# main_board_v1_2.net
KiCad netlist of a schematic drawn in EAGLE
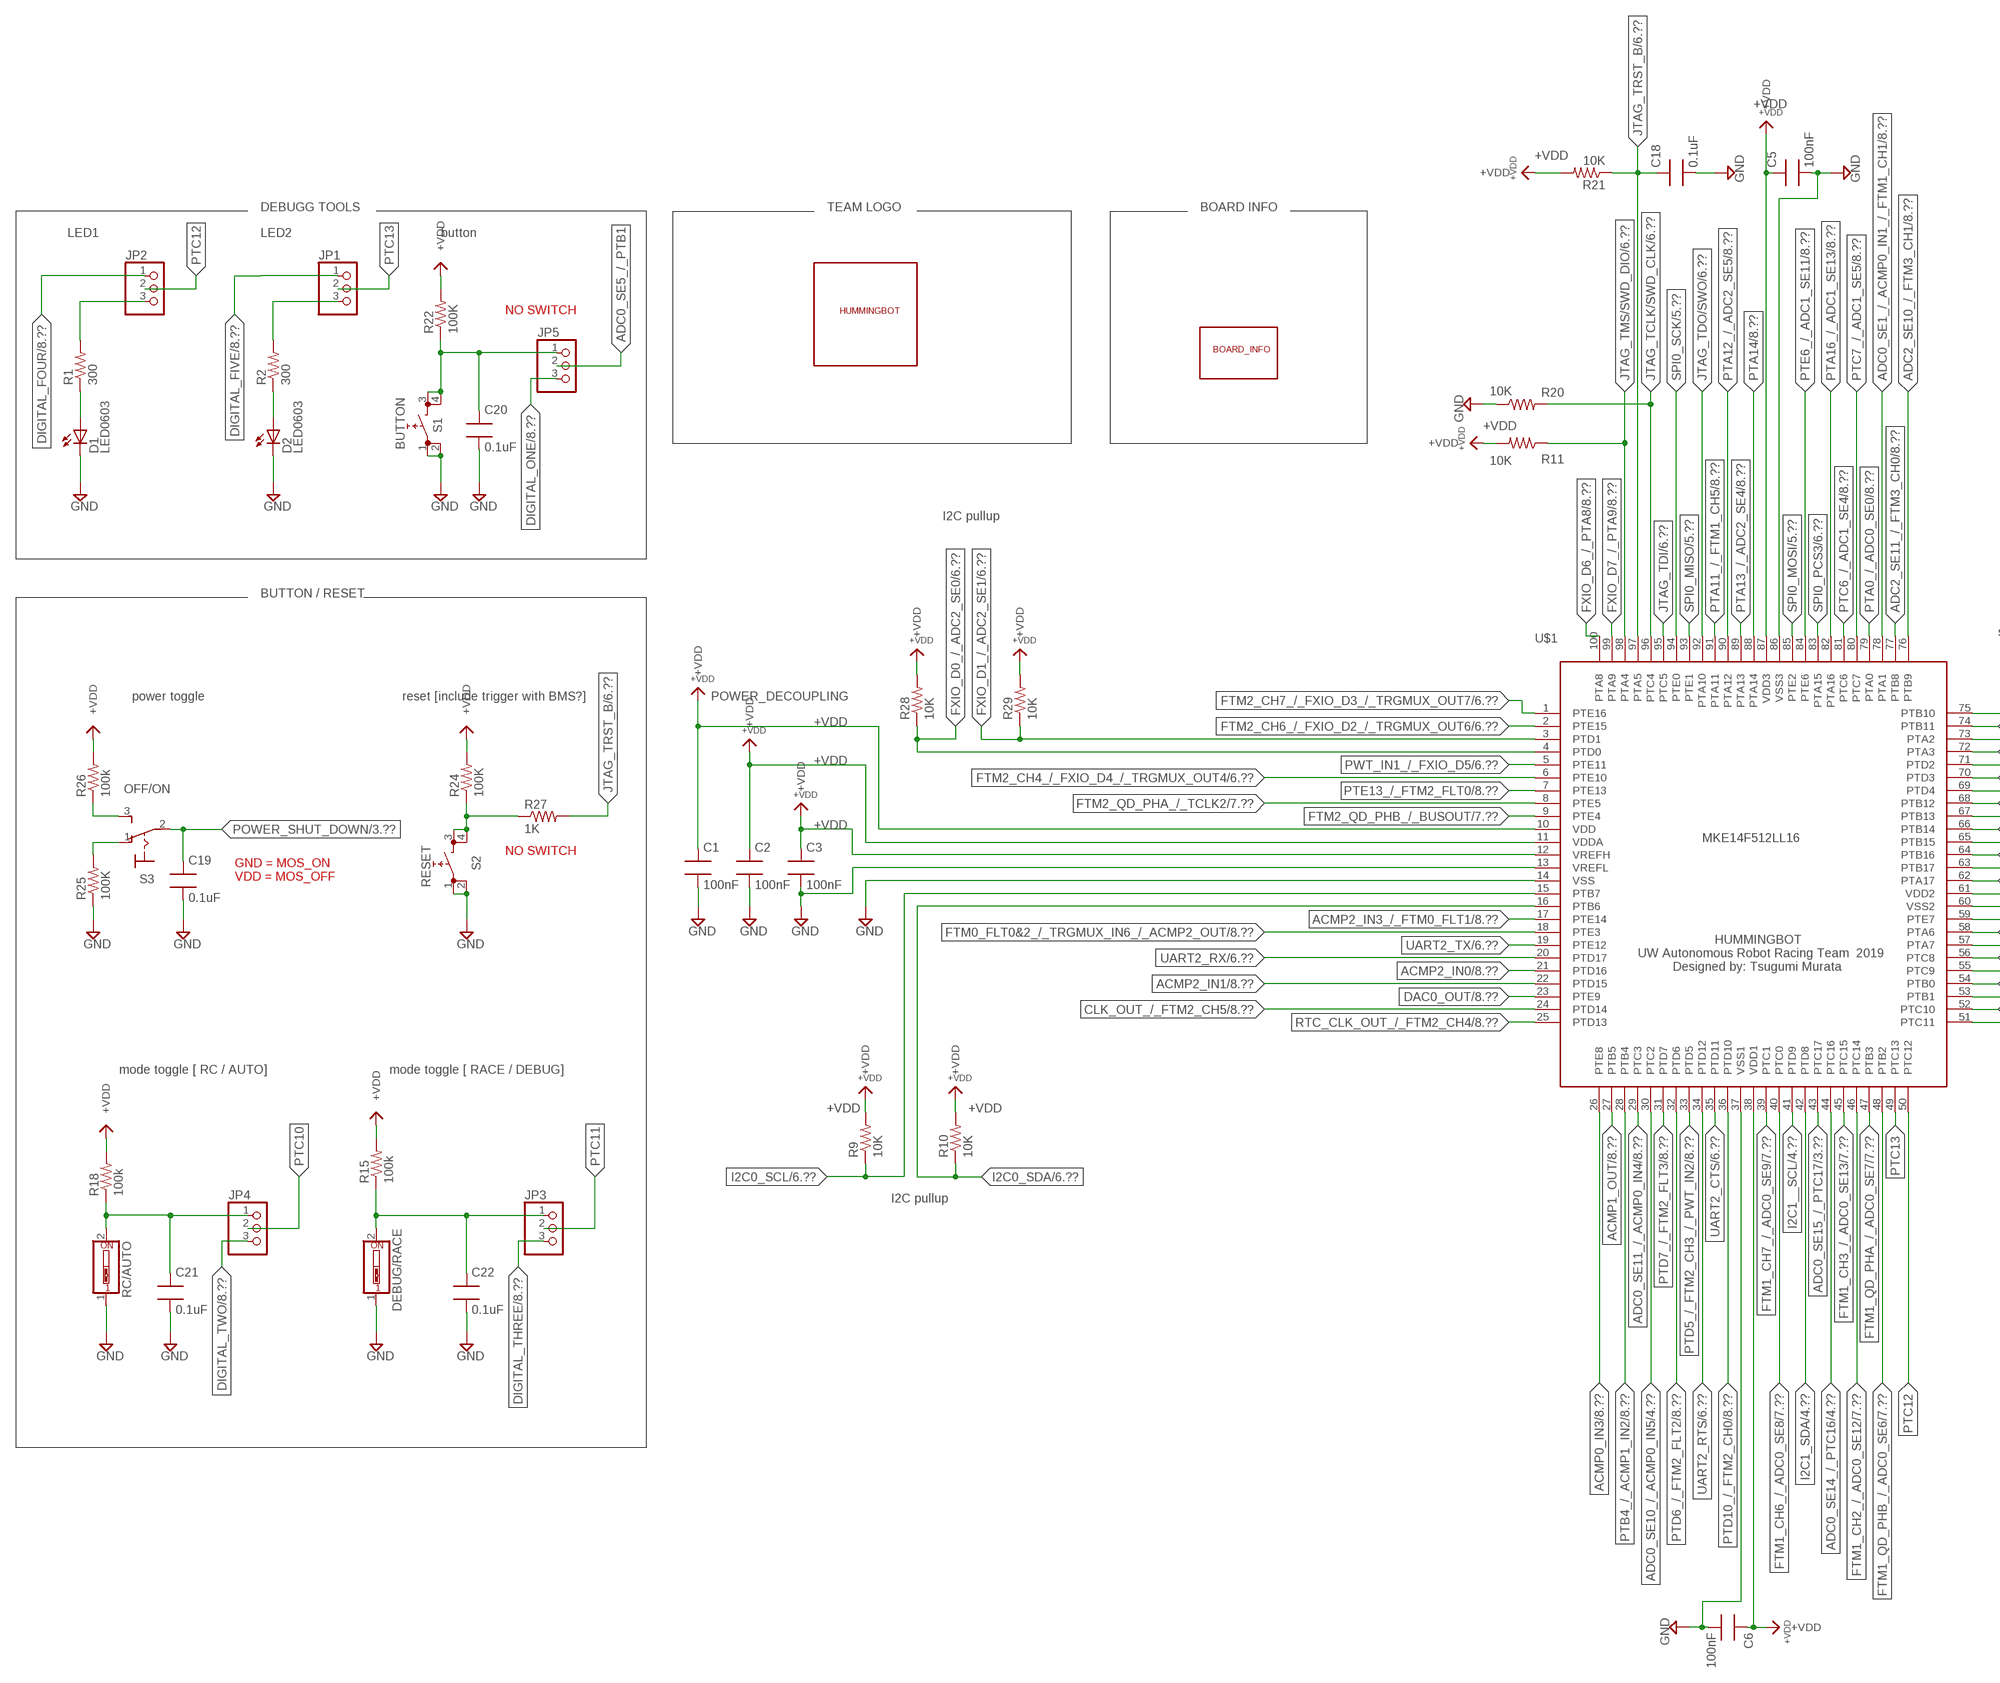
[diagram p0: schematic, sheet 1, part 1 of 2]
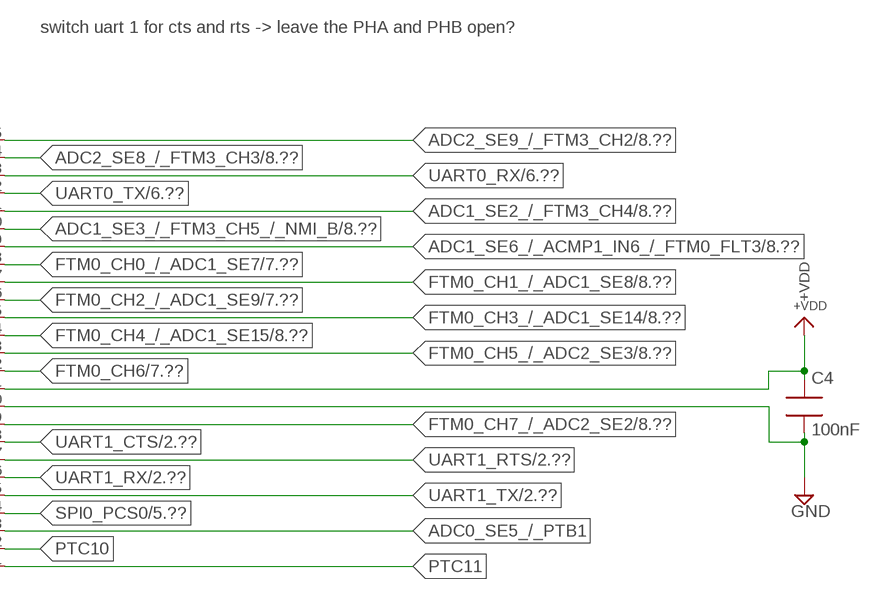
[diagram p1: schematic, sheet 1, part 2 of 2]
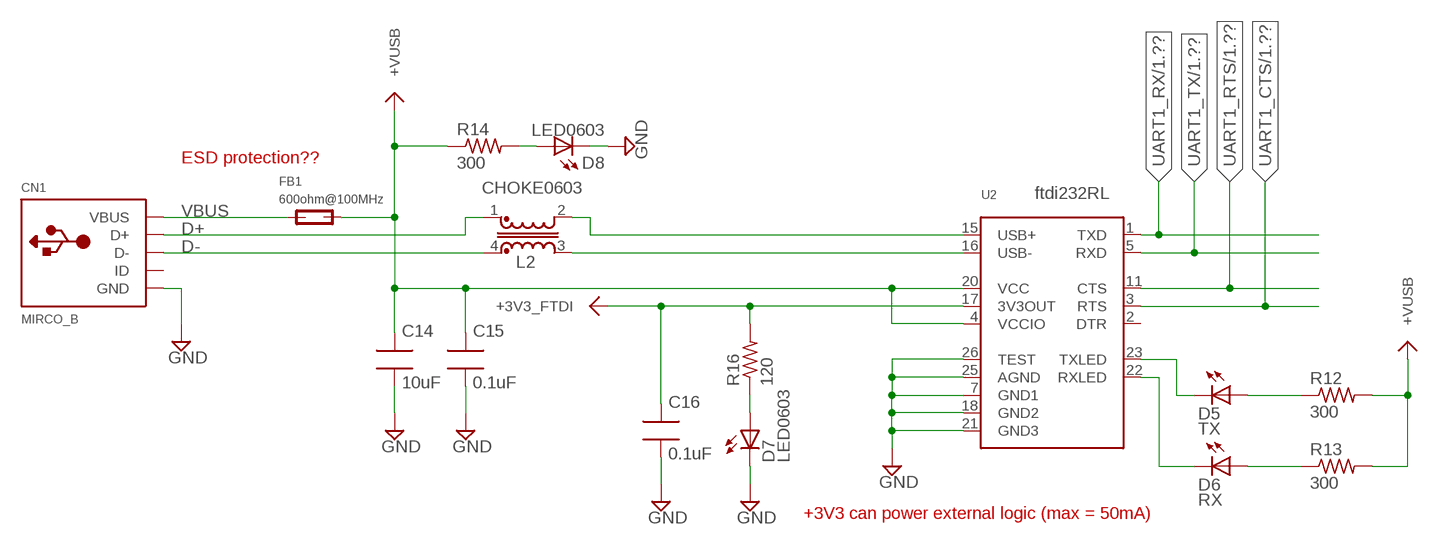
[diagram p2: schematic, sheet 2]
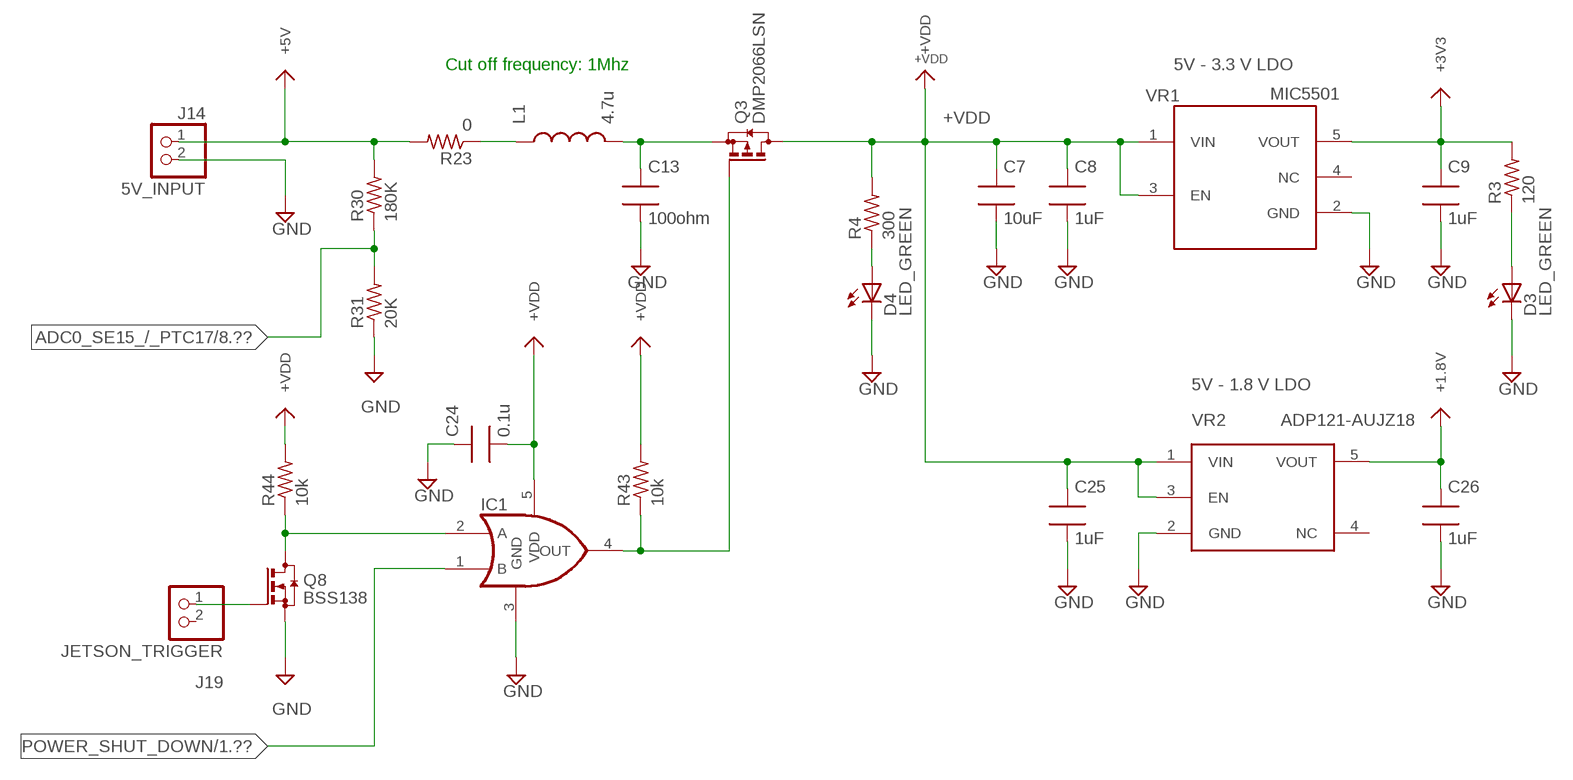
[diagram p3: schematic, sheet 3]
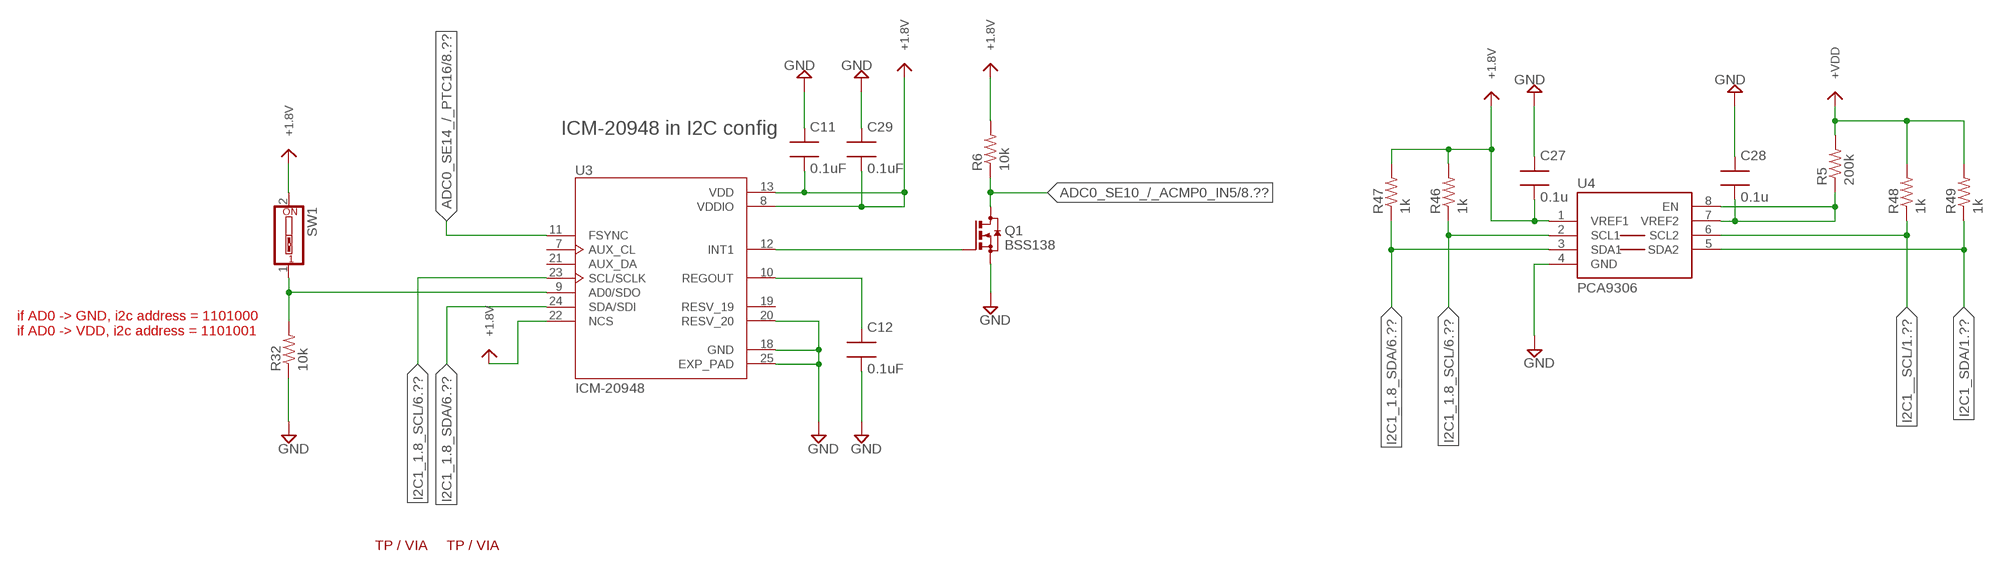
[diagram p4: schematic, sheet 4]
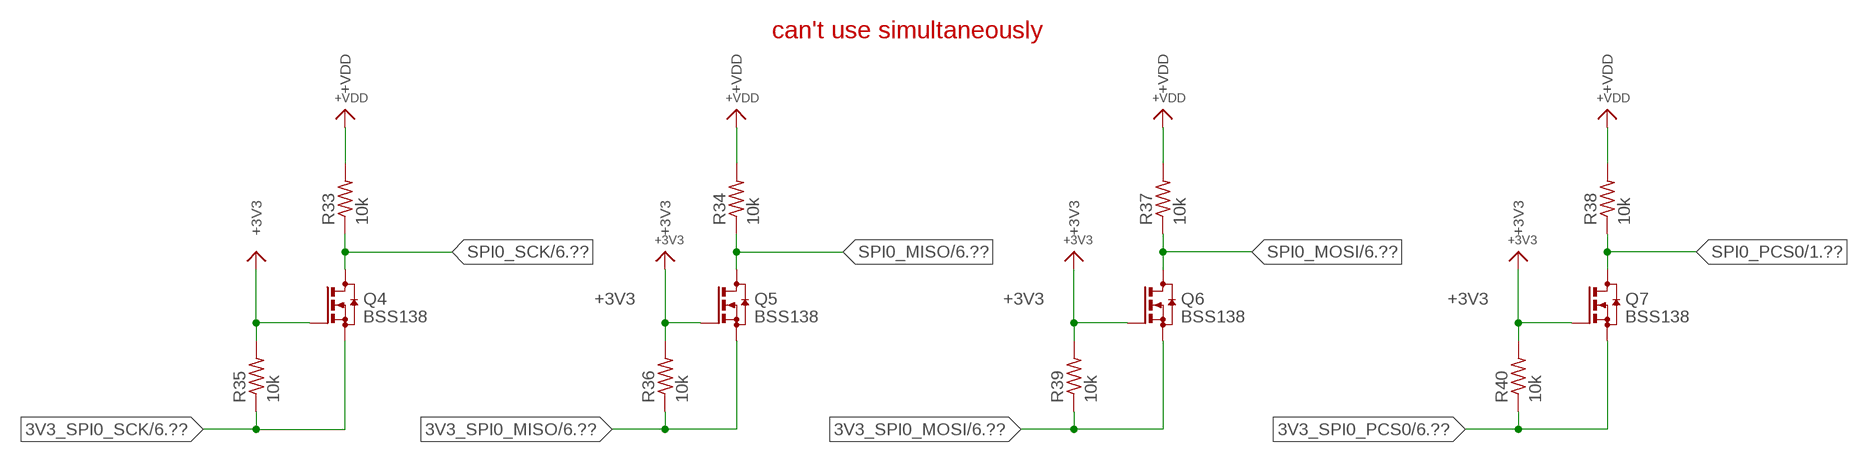
[diagram p5: schematic, sheet 5]
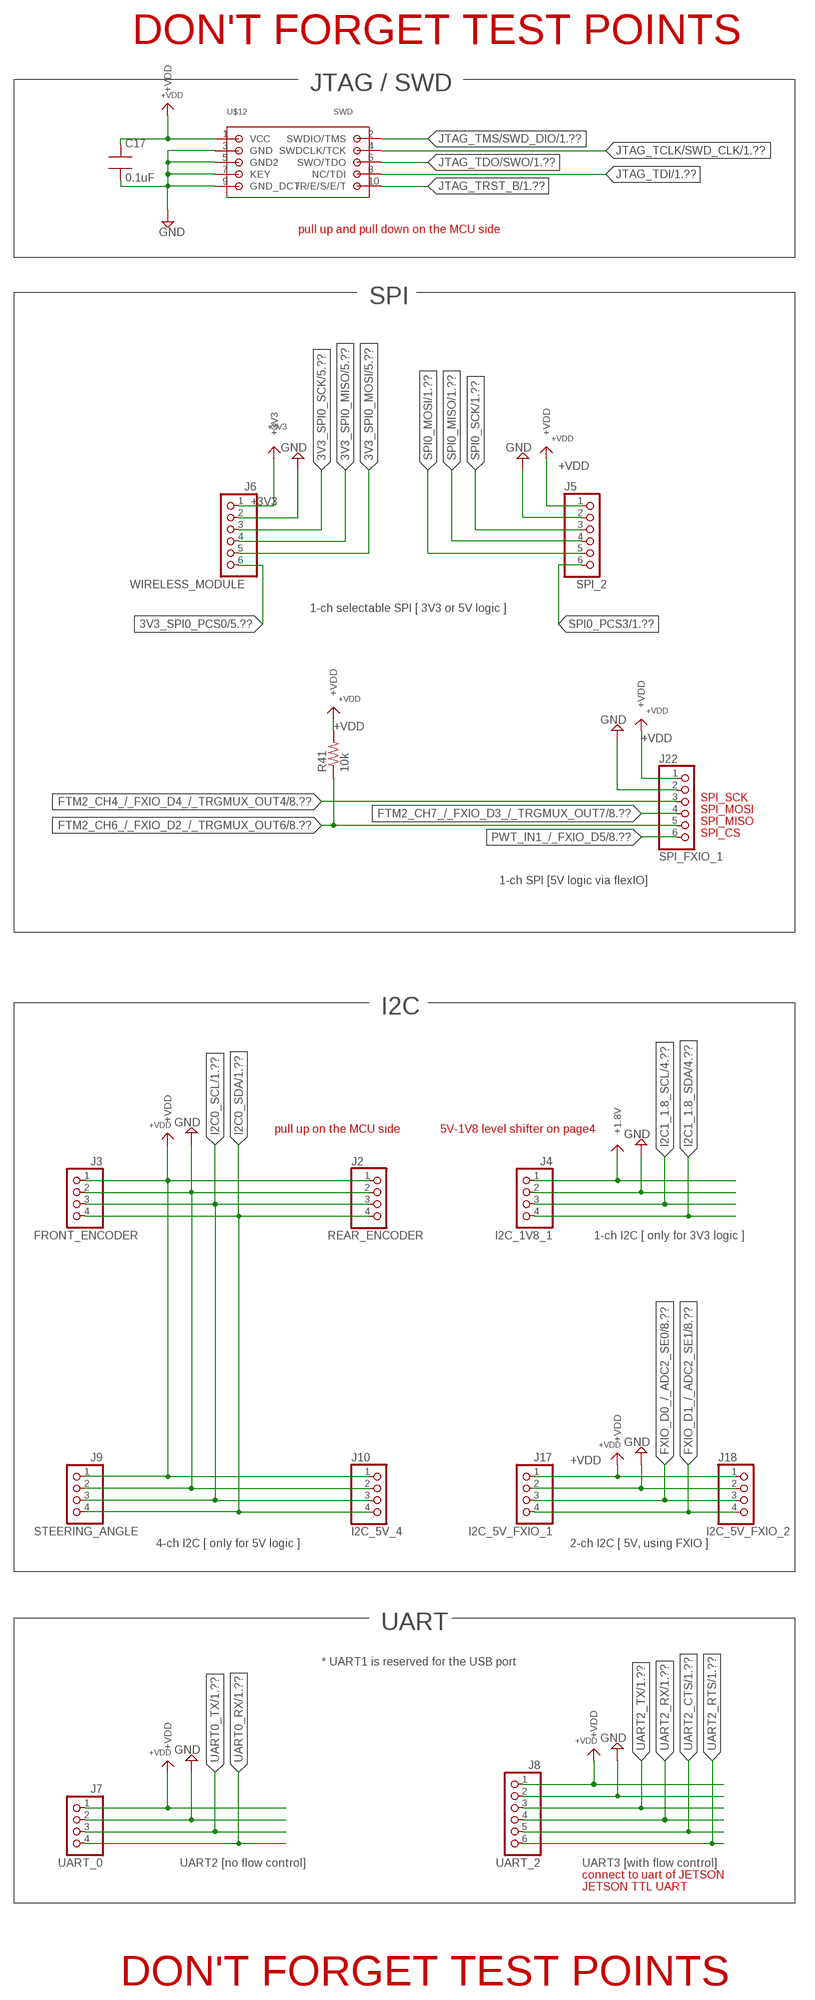
[diagram p6: schematic, sheet 6]
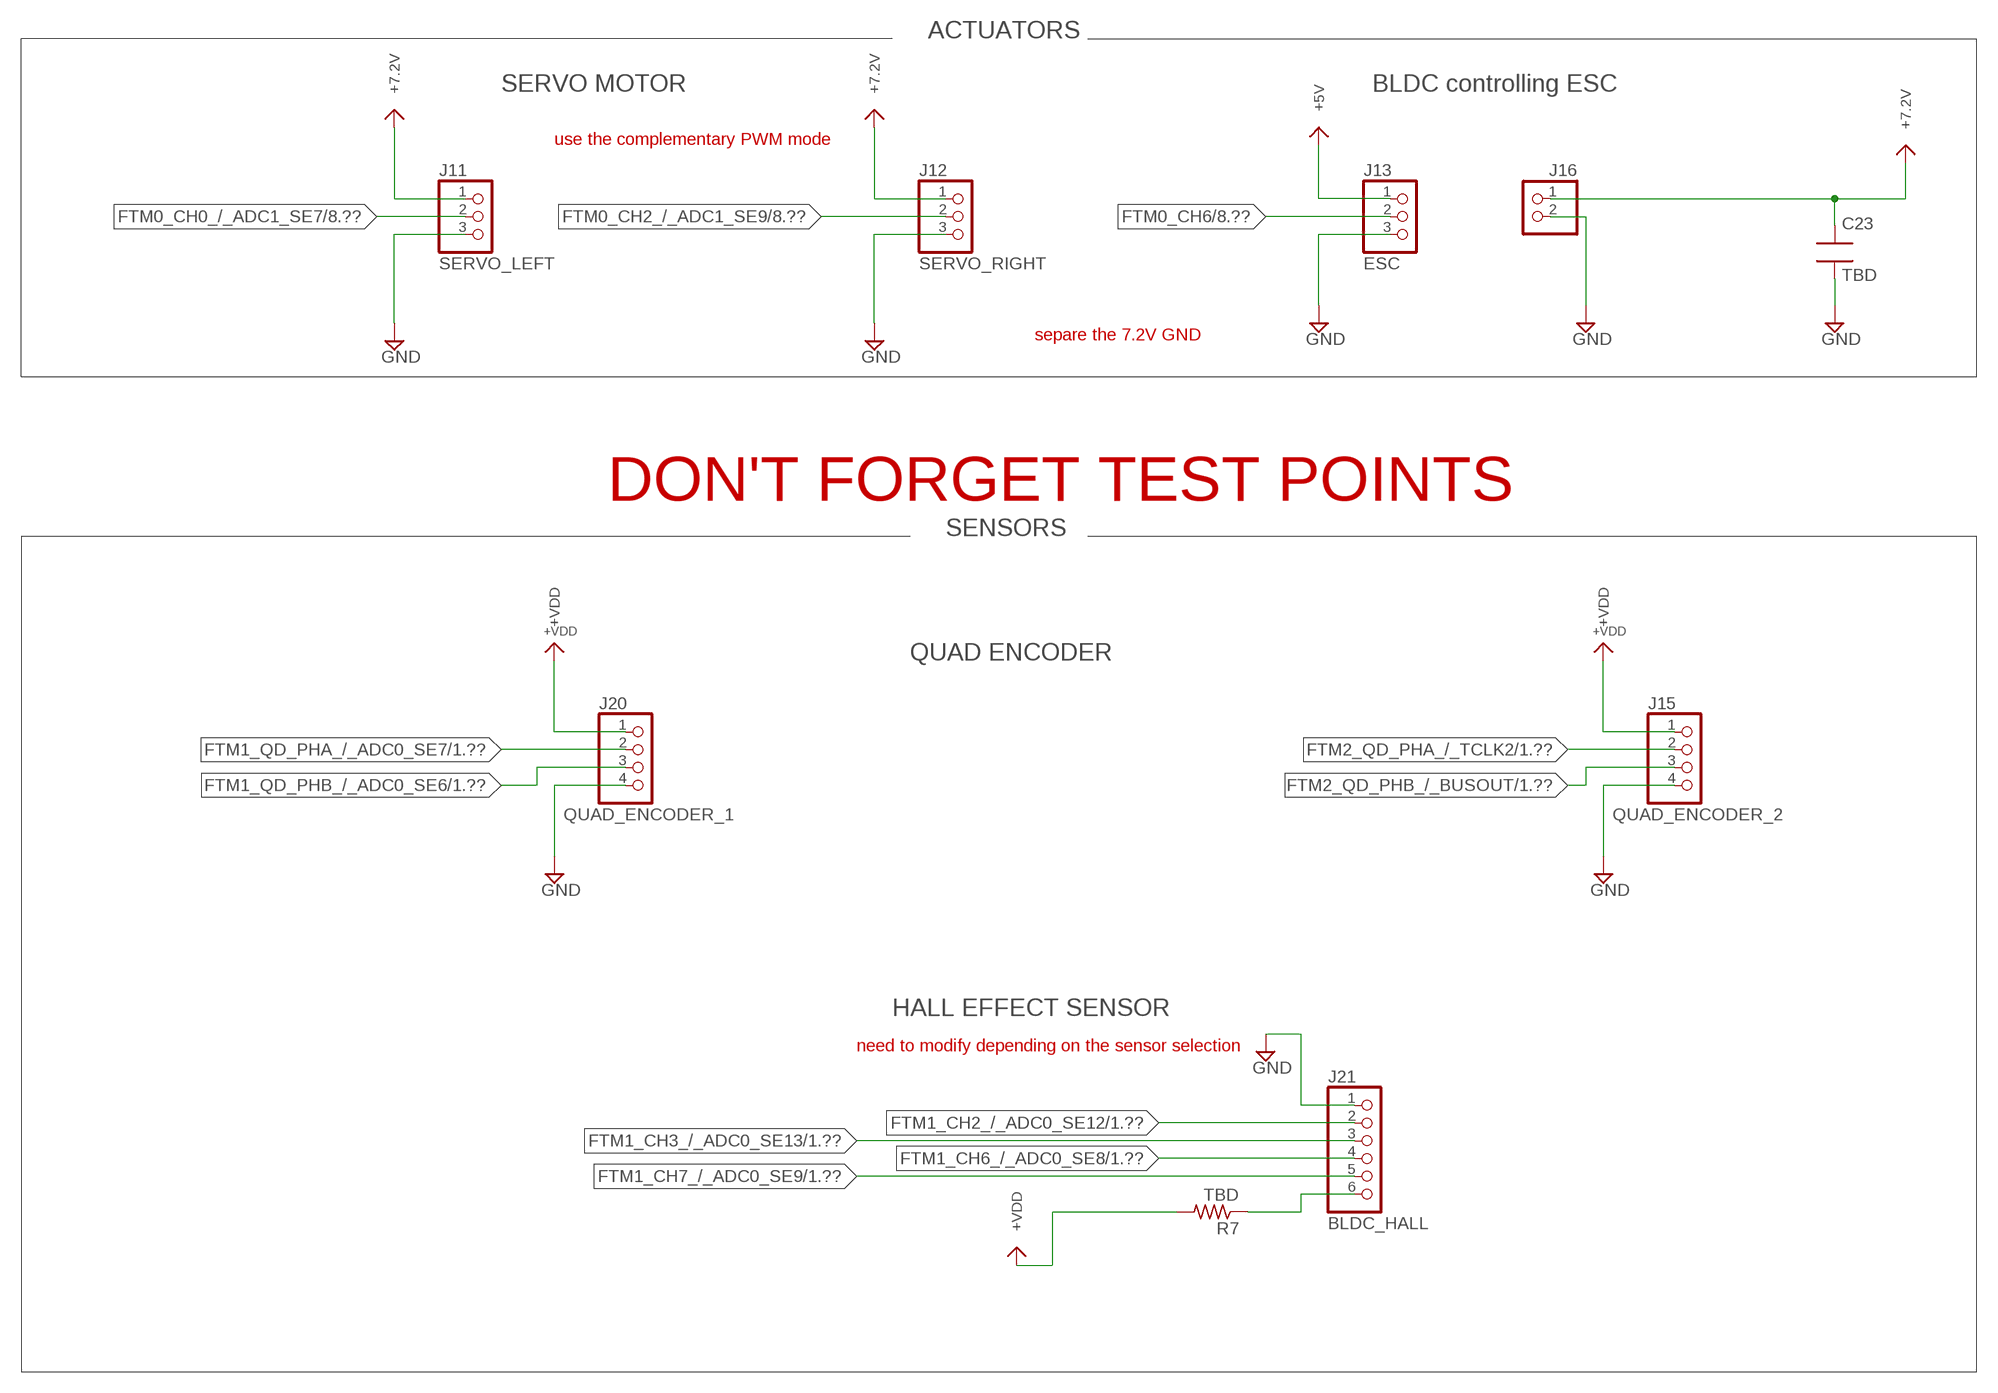
[diagram p7: schematic, sheet 7]
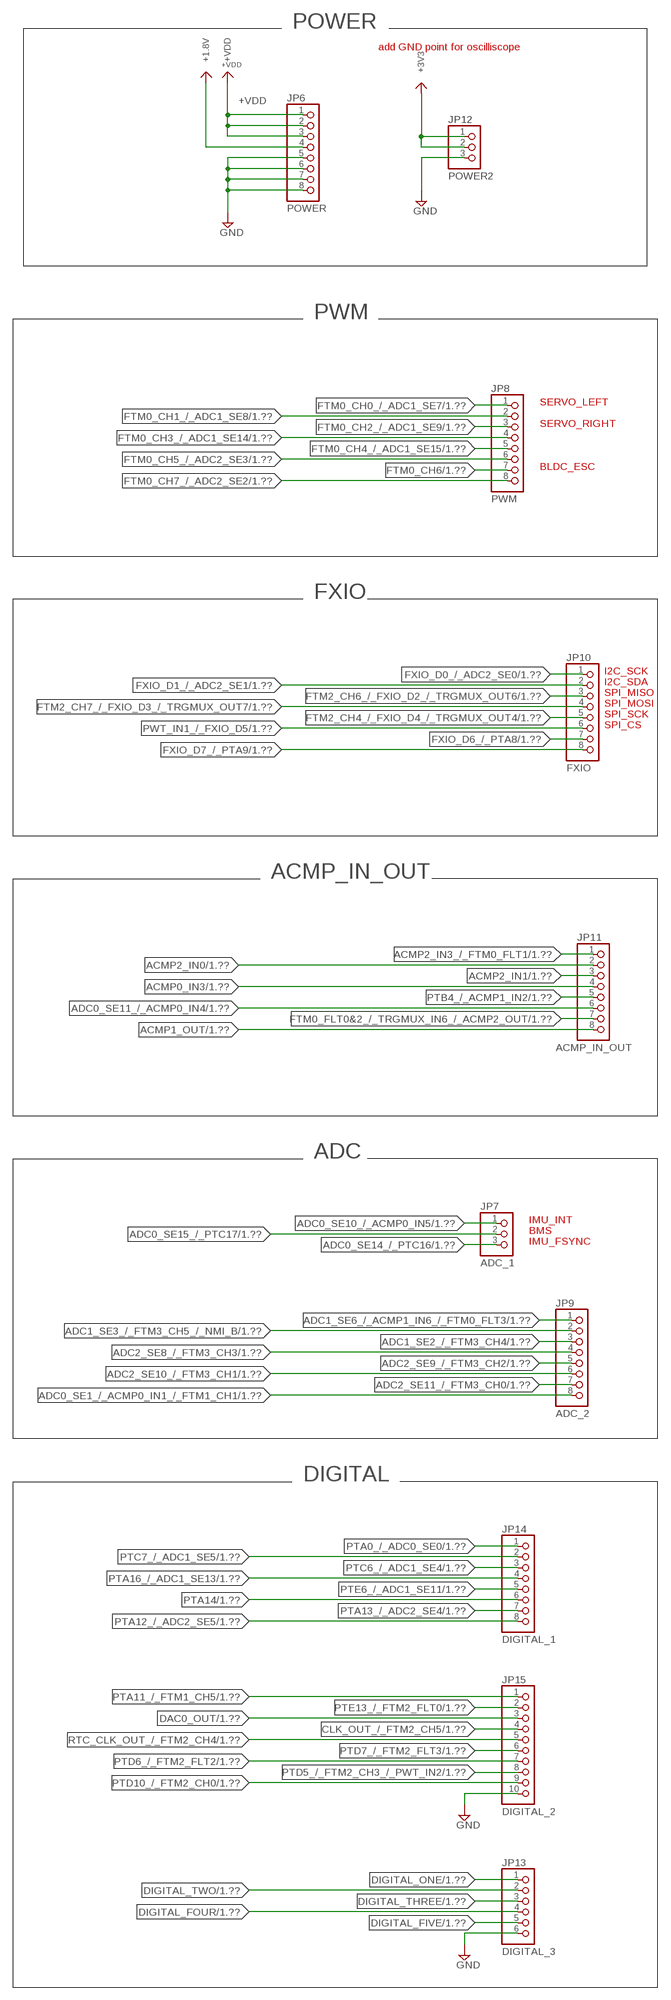
[diagram p8: schematic, sheet 8]

(export (version "E")
  (design (tool "Eeschema 10.0.6"))
  (components
    (comp (ref "C7")
      (value "10uF")
      (footprint "eagle-import:0603SMT")
      (libsource (lib "eagle-import") (part "CAP0603"))
    )
    (comp (ref "C8")
      (value "1uF")
      (footprint "eagle-import:0603SMT")
      (libsource (lib "eagle-import") (part "CAP0603"))
    )
    (comp (ref "C9")
      (value "1uF")
      (footprint "eagle-import:0603SMT")
      (libsource (lib "eagle-import") (part "CAP0603"))
    )
    (comp (ref "C13")
      (value "100ohm")
      (footprint "eagle-import:0603SMT")
      (libsource (lib "eagle-import") (part "CAP0603"))
    )
    (comp (ref "C24")
      (value "0.1u")
      (footprint "eagle-import:0603SMT")
      (libsource (lib "eagle-import") (part "CAP0603"))
    )
    (comp (ref "C25")
      (value "1uF")
      (footprint "eagle-import:0603SMT")
      (libsource (lib "eagle-import") (part "CAP0603"))
    )
    (comp (ref "C26")
      (value "1uF")
      (footprint "eagle-import:0603SMT")
      (libsource (lib "eagle-import") (part "CAP0603"))
    )
    (comp (ref "D3")
      (value "LED_GREEN")
      (footprint "eagle-import:0603SMT")
      (libsource (lib "eagle-import") (part "LED0603"))
    )
    (comp (ref "D4")
      (value "LED_GREEN")
      (footprint "eagle-import:0603SMT")
      (libsource (lib "eagle-import") (part "LED0603"))
    )
    (comp (ref "IC1")
      (value "OR_SC70-5")
      (footprint "eagle-import:SC70-5")
      (libsource (lib "eagle-import") (part "OR_SC70-5"))
    )
    (comp (ref "J14")
      (value "5V_INPUT")
      (footprint "eagle-import:JST_B2B-PH-K-S(LF)(SN)")
      (libsource (lib "eagle-import") (part "PINHEAD-2-VERTICAL"))
    )
    (comp (ref "J19")
      (value "JETSON_TRIGGER")
      (footprint "eagle-import:JST_B2B-PH-K-S(LF)(SN)")
      (libsource (lib "eagle-import") (part "PINHEAD-2-VERTICAL"))
    )
    (comp (ref "L1")
      (value "4.7u")
      (footprint "eagle-import:0603SMT")
      (libsource (lib "eagle-import") (part "IND0603"))
    )
    (comp (ref "Q3")
      (value "DMP2066LSN")
      (footprint "eagle-import:SOT23")
      (libsource (lib "eagle-import") (part "PMOS_SOT23"))
    )
    (comp (ref "Q8")
      (value "BSS138")
      (footprint "eagle-import:SOT23")
      (libsource (lib "eagle-import") (part "NMOS_SOT23"))
    )
    (comp (ref "R3")
      (value "120")
      (footprint "eagle-import:0603SMT")
      (libsource (lib "eagle-import") (part "RES0603"))
    )
    (comp (ref "R4")
      (value "300")
      (footprint "eagle-import:0603SMT")
      (libsource (lib "eagle-import") (part "RES0603"))
    )
    (comp (ref "R23")
      (value "0")
      (footprint "eagle-import:0603SMT")
      (libsource (lib "eagle-import") (part "RES0603"))
    )
    (comp (ref "R30")
      (value "180K")
      (footprint "eagle-import:0603SMT")
      (libsource (lib "eagle-import") (part "RES0603"))
    )
    (comp (ref "R31")
      (value "20K")
      (footprint "eagle-import:0603SMT")
      (libsource (lib "eagle-import") (part "RES0603"))
    )
    (comp (ref "R43")
      (value "10k")
      (footprint "eagle-import:0603SMT")
      (libsource (lib "eagle-import") (part "RES0603"))
    )
    (comp (ref "R44")
      (value "10k")
      (footprint "eagle-import:0603SMT")
      (libsource (lib "eagle-import") (part "RES0603"))
    )
    (comp (ref "VR1")
      (value "MIC5501")
      (footprint "eagle-import:SOT23-5")
      (libsource (lib "eagle-import") (part "MIC5501"))
    )
    (comp (ref "VR2")
      (value "ADP121-AUJZ18")
      (footprint "eagle-import:TSOT23-5")
      (libsource (lib "eagle-import") (part "ADP121"))
    )
    (comp (ref "C14")
      (value "10uF")
      (footprint "eagle-import:0603SMT")
      (libsource (lib "eagle-import") (part "CAP0603"))
    )
    (comp (ref "C15")
      (value "0.1uF")
      (footprint "eagle-import:0603SMT")
      (libsource (lib "eagle-import") (part "CAP0603"))
    )
    (comp (ref "C16")
      (value "0.1uF")
      (footprint "eagle-import:0603SMT")
      (libsource (lib "eagle-import") (part "CAP0603"))
    )
    (comp (ref "CN1")
      (value "MIRCO_B")
      (footprint "eagle-import:MICRO-USB")
      (libsource (lib "eagle-import") (part "MIRCO_B"))
    )
    (comp (ref "D5")
      (value "TX")
      (footprint "eagle-import:0603SMT")
      (libsource (lib "eagle-import") (part "LED0603"))
    )
    (comp (ref "D6")
      (value "RX")
      (footprint "eagle-import:0603SMT")
      (libsource (lib "eagle-import") (part "LED0603"))
    )
    (comp (ref "D7")
      (value "LED0603")
      (footprint "eagle-import:0603SMT")
      (libsource (lib "eagle-import") (part "LED0603"))
    )
    (comp (ref "D8")
      (value "LED0603")
      (footprint "eagle-import:0603SMT")
      (libsource (lib "eagle-import") (part "LED0603"))
    )
    (comp (ref "FB1")
      (value "600ohm@100MHz")
      (footprint "eagle-import:0603SMT")
      (libsource (lib "eagle-import") (part "FERRITE_BEAD"))
    )
    (comp (ref "L2")
      (value "CHOKE0603")
      (footprint "eagle-import:CHOKE0603")
      (libsource (lib "eagle-import") (part "CHOKE0603"))
    )
    (comp (ref "R12")
      (value "300")
      (footprint "eagle-import:0603SMT")
      (libsource (lib "eagle-import") (part "RES0603"))
    )
    (comp (ref "R13")
      (value "300")
      (footprint "eagle-import:0603SMT")
      (libsource (lib "eagle-import") (part "RES0603"))
    )
    (comp (ref "R14")
      (value "300")
      (footprint "eagle-import:0603SMT")
      (libsource (lib "eagle-import") (part "RES0603"))
    )
    (comp (ref "R16")
      (value "120")
      (footprint "eagle-import:0603SMT")
      (libsource (lib "eagle-import") (part "RES0603"))
    )
    (comp (ref "U2")
      (value "FT232RLSSOP28")
      (footprint "eagle-import:SSOP28DB")
      (libsource (lib "eagle-import") (part "FT232RLSSOP28"))
    )
    (comp (ref "C23")
      (value "TBD")
      (footprint "eagle-import:0603SMT")
      (libsource (lib "eagle-import") (part "CAP0603"))
    )
    (comp (ref "J11")
      (value "SERVO_LEFT")
      (footprint "eagle-import:JST_B3B-PH-K-S(LF)(SN)")
      (libsource (lib "eagle-import") (part "PINHEAD-3-VERTICAL"))
    )
    (comp (ref "J12")
      (value "SERVO_RIGHT")
      (footprint "eagle-import:JST_B3B-PH-K-S(LF)(SN)")
      (libsource (lib "eagle-import") (part "PINHEAD-3-VERTICAL"))
    )
    (comp (ref "J13")
      (value "ESC")
      (footprint "eagle-import:JST_B3B-PH-K-S(LF)(SN)")
      (libsource (lib "eagle-import") (part "PINHEAD-3-VERTICAL"))
    )
    (comp (ref "J15")
      (value "QUAD_ENCODER_2")
      (footprint "eagle-import:JST_B4B-PH-K-S(LF)(SN)")
      (libsource (lib "eagle-import") (part "PINHEAD-4-VERTICAL"))
    )
    (comp (ref "J16")
      (value "7.2V_INPUT")
      (footprint "eagle-import:JST_B2B-PH-K-S(LF)(SN)")
      (libsource (lib "eagle-import") (part "PINHEAD-2-VERTICAL"))
    )
    (comp (ref "J20")
      (value "QUAD_ENCODER_1")
      (footprint "eagle-import:JST_B4B-PH-K-S(LF)(SN)")
      (libsource (lib "eagle-import") (part "PINHEAD-4-VERTICAL"))
    )
    (comp (ref "J21")
      (value "BLDC_HALL")
      (footprint "eagle-import:JST_B6B-PH-K-S(LF)(SN)")
      (libsource (lib "eagle-import") (part "PINHEAD-6-VERTICAL"))
    )
    (comp (ref "R7")
      (value "TBD")
      (footprint "eagle-import:0603SMT")
      (libsource (lib "eagle-import") (part "RES0603"))
    )
    (comp (ref "C17")
      (value "0.1uF")
      (footprint "eagle-import:0603SMT")
      (fields (field (name "SPICEPREFIX") "C"))
      (libsource (lib "eagle-import") (part "CAP0603"))
    )
    (comp (ref "J2")
      (value "REAR_ENCODER")
      (footprint "eagle-import:JST_B4B-PH-K-S(LF)(SN)")
      (libsource (lib "eagle-import") (part "PINHEAD-4-VERTICAL"))
    )
    (comp (ref "J3")
      (value "FRONT_ENCODER")
      (footprint "eagle-import:JST_B4B-PH-K-S(LF)(SN)")
      (libsource (lib "eagle-import") (part "PINHEAD-4-VERTICAL"))
    )
    (comp (ref "J4")
      (value "I2C_1V8_1")
      (footprint "eagle-import:JST_B4B-PH-K-S(LF)(SN)")
      (libsource (lib "eagle-import") (part "PINHEAD-4-VERTICAL"))
    )
    (comp (ref "J5")
      (value "SPI_2")
      (footprint "eagle-import:JST_B6B-PH-K-S(LF)(SN)")
      (libsource (lib "eagle-import") (part "PINHEAD-6-VERTICAL"))
    )
    (comp (ref "J6")
      (value "WIRELESS_MODULE")
      (footprint "eagle-import:JST_B6B-PH-K-S(LF)(SN)")
      (libsource (lib "eagle-import") (part "PINHEAD-6-VERTICAL"))
    )
    (comp (ref "J7")
      (value "UART_0")
      (footprint "eagle-import:JST_B4B-PH-K-S(LF)(SN)")
      (libsource (lib "eagle-import") (part "PINHEAD-4-VERTICAL"))
    )
    (comp (ref "J8")
      (value "UART_2")
      (footprint "eagle-import:JST_B6B-PH-K-S(LF)(SN)")
      (libsource (lib "eagle-import") (part "PINHEAD-6-VERTICAL"))
    )
    (comp (ref "J9")
      (value "STEERING_ANGLE")
      (footprint "eagle-import:JST_B4B-PH-K-S(LF)(SN)")
      (libsource (lib "eagle-import") (part "PINHEAD-4-VERTICAL"))
    )
    (comp (ref "J10")
      (value "I2C_5V_4")
      (footprint "eagle-import:JST_B4B-PH-K-S(LF)(SN)")
      (libsource (lib "eagle-import") (part "PINHEAD-4-VERTICAL"))
    )
    (comp (ref "J17")
      (value "I2C_5V_FXIO_1")
      (footprint "eagle-import:JST_B4B-PH-K-S(LF)(SN)")
      (libsource (lib "eagle-import") (part "PINHEAD-4-VERTICAL"))
    )
    (comp (ref "J18")
      (value "I2C_5V_FXIO_2")
      (footprint "eagle-import:JST_B4B-PH-K-S(LF)(SN)")
      (libsource (lib "eagle-import") (part "PINHEAD-4-VERTICAL"))
    )
    (comp (ref "J22")
      (value "SPI_FXIO_1")
      (footprint "eagle-import:JST_B6B-PH-K-S(LF)(SN)")
      (libsource (lib "eagle-import") (part "PINHEAD-6-VERTICAL"))
    )
    (comp (ref "R41")
      (value "10k")
      (footprint "eagle-import:0603SMT")
      (libsource (lib "eagle-import") (part "RES0603"))
    )
    (comp (ref "U$12")
      (value "SWD")
      (footprint "eagle-import:SWD_1.27MM")
      (libsource (lib "eagle-import") (part "SWD_1.27MM"))
    )
    (comp (ref "Q4")
      (value "BSS138")
      (footprint "eagle-import:SOT23")
      (libsource (lib "eagle-import") (part "NMOS_SOT23"))
    )
    (comp (ref "Q5")
      (value "BSS138")
      (footprint "eagle-import:SOT23")
      (libsource (lib "eagle-import") (part "NMOS_SOT23"))
    )
    (comp (ref "Q6")
      (value "BSS138")
      (footprint "eagle-import:SOT23")
      (libsource (lib "eagle-import") (part "NMOS_SOT23"))
    )
    (comp (ref "Q7")
      (value "BSS138")
      (footprint "eagle-import:SOT23")
      (libsource (lib "eagle-import") (part "NMOS_SOT23"))
    )
    (comp (ref "R33")
      (value "10k")
      (footprint "eagle-import:0603SMT")
      (libsource (lib "eagle-import") (part "RES0603"))
    )
    (comp (ref "R34")
      (value "10k")
      (footprint "eagle-import:0603SMT")
      (libsource (lib "eagle-import") (part "RES0603"))
    )
    (comp (ref "R35")
      (value "10k")
      (footprint "eagle-import:0603SMT")
      (libsource (lib "eagle-import") (part "RES0603"))
    )
    (comp (ref "R36")
      (value "10k")
      (footprint "eagle-import:0603SMT")
      (libsource (lib "eagle-import") (part "RES0603"))
    )
    (comp (ref "R37")
      (value "10k")
      (footprint "eagle-import:0603SMT")
      (libsource (lib "eagle-import") (part "RES0603"))
    )
    (comp (ref "R38")
      (value "10k")
      (footprint "eagle-import:0603SMT")
      (libsource (lib "eagle-import") (part "RES0603"))
    )
    (comp (ref "R39")
      (value "10k")
      (footprint "eagle-import:0603SMT")
      (libsource (lib "eagle-import") (part "RES0603"))
    )
    (comp (ref "R40")
      (value "10k")
      (footprint "eagle-import:0603SMT")
      (libsource (lib "eagle-import") (part "RES0603"))
    )
    (comp (ref "C1")
      (value "100nF")
      (footprint "eagle-import:0603SMT")
      (libsource (lib "eagle-import") (part "CAP0603"))
    )
    (comp (ref "C2")
      (value "100nF")
      (footprint "eagle-import:0603SMT")
      (libsource (lib "eagle-import") (part "CAP0603"))
    )
    (comp (ref "C3")
      (value "100nF")
      (footprint "eagle-import:0603SMT")
      (libsource (lib "eagle-import") (part "CAP0603"))
    )
    (comp (ref "C4")
      (value "100nF")
      (footprint "eagle-import:0603SMT")
      (libsource (lib "eagle-import") (part "CAP0603"))
    )
    (comp (ref "C5")
      (value "100nF")
      (footprint "eagle-import:0603SMT")
      (libsource (lib "eagle-import") (part "CAP0603"))
    )
    (comp (ref "C6")
      (value "100nF")
      (footprint "eagle-import:0603SMT")
      (libsource (lib "eagle-import") (part "CAP0603"))
    )
    (comp (ref "C18")
      (value "0.1uF")
      (footprint "eagle-import:0603SMT")
      (libsource (lib "eagle-import") (part "CAP0603"))
    )
    (comp (ref "C19")
      (value "0.1uF")
      (footprint "eagle-import:0603SMT")
      (libsource (lib "eagle-import") (part "CAP0603"))
    )
    (comp (ref "C20")
      (value "0.1uF")
      (footprint "eagle-import:0603SMT")
      (libsource (lib "eagle-import") (part "CAP0603"))
    )
    (comp (ref "C21")
      (value "0.1uF")
      (footprint "eagle-import:0603SMT")
      (libsource (lib "eagle-import") (part "CAP0603"))
    )
    (comp (ref "C22")
      (value "0.1uF")
      (footprint "eagle-import:0603SMT")
      (libsource (lib "eagle-import") (part "CAP0603"))
    )
    (comp (ref "D1")
      (value "LED0603")
      (footprint "eagle-import:0603SMT")
      (libsource (lib "eagle-import") (part "LED0603"))
    )
    (comp (ref "D2")
      (value "LED0603")
      (footprint "eagle-import:0603SMT")
      (libsource (lib "eagle-import") (part "LED0603"))
    )
    (comp (ref "DEBUG/RACE")
      (value "SW_DIP-1")
      (footprint "eagle-import:EDG-01")
      (libsource (lib "eagle-import") (part "SW_DIP-1"))
    )
    (comp (ref "JP1")
      (value "PINHD-1X3")
      (footprint "eagle-import:1X03")
      (libsource (lib "eagle-import") (part "PINHD-1X3"))
    )
    (comp (ref "JP2")
      (value "PINHD-1X3")
      (footprint "eagle-import:1X03")
      (libsource (lib "eagle-import") (part "PINHD-1X3"))
    )
    (comp (ref "JP3")
      (value "PINHD-1X3")
      (footprint "eagle-import:1X03")
      (libsource (lib "eagle-import") (part "PINHD-1X3"))
    )
    (comp (ref "JP4")
      (value "PINHD-1X3")
      (footprint "eagle-import:1X03")
      (libsource (lib "eagle-import") (part "PINHD-1X3"))
    )
    (comp (ref "JP5")
      (value "PINHD-1X3")
      (footprint "eagle-import:1X03")
      (libsource (lib "eagle-import") (part "PINHD-1X3"))
    )
    (comp (ref "R1")
      (value "300")
      (footprint "eagle-import:0603SMT")
      (libsource (lib "eagle-import") (part "RES0603"))
    )
    (comp (ref "R2")
      (value "300")
      (footprint "eagle-import:0603SMT")
      (libsource (lib "eagle-import") (part "RES0603"))
    )
    (comp (ref "R9")
      (value "10K")
      (footprint "eagle-import:0603SMT")
      (libsource (lib "eagle-import") (part "RES0603"))
    )
    (comp (ref "R10")
      (value "10K")
      (footprint "eagle-import:0603SMT")
      (libsource (lib "eagle-import") (part "RES0603"))
    )
    (comp (ref "R11")
      (value "10K")
      (footprint "eagle-import:0603SMT")
      (libsource (lib "eagle-import") (part "RES0603"))
    )
    (comp (ref "R15")
      (value "100k")
      (footprint "eagle-import:0603SMT")
      (libsource (lib "eagle-import") (part "RES0603"))
    )
    (comp (ref "R18")
      (value "100k")
      (footprint "eagle-import:0603SMT")
      (libsource (lib "eagle-import") (part "RES0603"))
    )
    (comp (ref "R20")
      (value "10K")
      (footprint "eagle-import:0603SMT")
      (libsource (lib "eagle-import") (part "RES0603"))
    )
    (comp (ref "R21")
      (value "10K")
      (footprint "eagle-import:0603SMT")
      (libsource (lib "eagle-import") (part "RES0603"))
    )
    (comp (ref "R22")
      (value "100K")
      (footprint "eagle-import:0603SMT")
      (libsource (lib "eagle-import") (part "RES0603"))
    )
    (comp (ref "R24")
      (value "100K")
      (footprint "eagle-import:0603SMT")
      (libsource (lib "eagle-import") (part "RES0603"))
    )
    (comp (ref "R25")
      (value "100K")
      (footprint "eagle-import:0603SMT")
      (libsource (lib "eagle-import") (part "RES0603"))
    )
    (comp (ref "R26")
      (value "100k")
      (footprint "eagle-import:0603SMT")
      (libsource (lib "eagle-import") (part "RES0603"))
    )
    (comp (ref "R27")
      (value "1K")
      (footprint "eagle-import:0603SMT")
      (libsource (lib "eagle-import") (part "RES0603"))
    )
    (comp (ref "R28")
      (value "10K")
      (footprint "eagle-import:0603SMT")
      (libsource (lib "eagle-import") (part "RES0603"))
    )
    (comp (ref "R29")
      (value "10K")
      (footprint "eagle-import:0603SMT")
      (libsource (lib "eagle-import") (part "RES0603"))
    )
    (comp (ref "RC/AUTO")
      (value "SW_DIP-1")
      (footprint "eagle-import:EDG-01")
      (libsource (lib "eagle-import") (part "SW_DIP-1"))
    )
    (comp (ref "S1")
      (value "BUTTON")
      (footprint "eagle-import:TACT_SWITCH_SMT")
      (libsource (lib "eagle-import") (part "TACT_SWITCH_6X6_SMT"))
    )
    (comp (ref "S2")
      (value "RESET")
      (footprint "eagle-import:TACT_SWITCH_SMT")
      (libsource (lib "eagle-import") (part "TACT_SWITCH_6X6_SMT"))
    )
    (comp (ref "S3")
      (value "OFF/ON")
      (footprint "eagle-import:M9040P")
      (libsource (lib "eagle-import") (part "M9040P"))
    )
    (comp (ref "U$1")
      (value "MKE14F512LL16")
      (footprint "eagle-import:LQFP100")
      (libsource (lib "eagle-import") (part "MKE14F512LL16"))
    )
    (comp (ref "U$38")
      (value "BOARD_INFO")
      (footprint "eagle-import:BOARD_INFO")
      (libsource (lib "eagle-import") (part "BOARD_INFO"))
    )
    (comp (ref "U$44")
      (value "TEAM_LOGO")
      (footprint "eagle-import:TEAM_LOGO")
      (libsource (lib "eagle-import") (part "TEAM_LOGO"))
    )
    (comp (ref "C11")
      (value "0.1uF")
      (footprint "eagle-import:0603SMT")
      (fields (field (name "SPICEPREFIX") "C"))
      (libsource (lib "eagle-import") (part "CAP0603"))
    )
    (comp (ref "C12")
      (value "0.1uF")
      (footprint "eagle-import:0603SMT")
      (libsource (lib "eagle-import") (part "CAP0603"))
    )
    (comp (ref "C27")
      (value "0.1u")
      (footprint "eagle-import:0603SMT")
      (libsource (lib "eagle-import") (part "CAP0603"))
    )
    (comp (ref "C28")
      (value "0.1u")
      (footprint "eagle-import:0603SMT")
      (libsource (lib "eagle-import") (part "CAP0603"))
    )
    (comp (ref "C29")
      (value "0.1uF")
      (footprint "eagle-import:0603SMT")
      (fields (field (name "SPICEPREFIX") "C"))
      (libsource (lib "eagle-import") (part "CAP0603"))
    )
    (comp (ref "Q1")
      (value "BSS138")
      (footprint "eagle-import:SOT23")
      (libsource (lib "eagle-import") (part "NMOS_SOT23"))
    )
    (comp (ref "R5")
      (value "200k")
      (footprint "eagle-import:0603SMT")
      (libsource (lib "eagle-import") (part "RES0603"))
    )
    (comp (ref "R6")
      (value "10k")
      (footprint "eagle-import:0603SMT")
      (libsource (lib "eagle-import") (part "RES0603"))
    )
    (comp (ref "R32")
      (value "10k")
      (footprint "eagle-import:0603SMT")
      (libsource (lib "eagle-import") (part "RES0603"))
    )
    (comp (ref "R46")
      (value "1k")
      (footprint "eagle-import:0603SMT")
      (libsource (lib "eagle-import") (part "RES0603"))
    )
    (comp (ref "R47")
      (value "1k")
      (footprint "eagle-import:0603SMT")
      (libsource (lib "eagle-import") (part "RES0603"))
    )
    (comp (ref "R48")
      (value "1k")
      (footprint "eagle-import:0603SMT")
      (libsource (lib "eagle-import") (part "RES0603"))
    )
    (comp (ref "R49")
      (value "1k")
      (footprint "eagle-import:0603SMT")
      (libsource (lib "eagle-import") (part "RES0603"))
    )
    (comp (ref "SW1")
      (value "SW_DIP-1")
      (footprint "eagle-import:EDG-01")
      (libsource (lib "eagle-import") (part "SW_DIP-1"))
    )
    (comp (ref "U3")
      (value "ICM-20948")
      (footprint "eagle-import:QFN40P300X300X105-25N")
      (fields (field (name "MF") "TDK InvenSense"))
      (libsource (lib "eagle-import") (part "ICM-20948"))
    )
    (comp (ref "U4")
      (value "PCA9306")
      (footprint "eagle-import:PSOP-8")
      (fields (field (name "MF") "Texas Instruments"))
      (libsource (lib "eagle-import") (part "PCA9306"))
    )
    (comp (ref "JP6")
      (value "POWER")
      (footprint "eagle-import:1X08-BIG")
      (libsource (lib "eagle-import") (part "PINHD-1X8BIG"))
    )
    (comp (ref "JP7")
      (value "ADC_1")
      (footprint "eagle-import:1X03")
      (libsource (lib "eagle-import") (part "PINHD-1X3"))
    )
    (comp (ref "JP8")
      (value "PWM")
      (footprint "eagle-import:1X08-BIG")
      (libsource (lib "eagle-import") (part "PINHD-1X8BIG"))
    )
    (comp (ref "JP9")
      (value "ADC_2")
      (footprint "eagle-import:1X08-BIG")
      (libsource (lib "eagle-import") (part "PINHD-1X8BIG"))
    )
    (comp (ref "JP10")
      (value "FXIO")
      (footprint "eagle-import:1X08-BIG")
      (libsource (lib "eagle-import") (part "PINHD-1X8BIG"))
    )
    (comp (ref "JP11")
      (value "ACMP_IN_OUT")
      (footprint "eagle-import:1X08-BIG")
      (libsource (lib "eagle-import") (part "PINHD-1X8BIG"))
    )
    (comp (ref "JP12")
      (value "POWER2")
      (footprint "eagle-import:1X03")
      (libsource (lib "eagle-import") (part "PINHD-1X3"))
    )
    (comp (ref "JP13")
      (value "DIGITAL_3")
      (footprint "eagle-import:1X06-BIG")
      (libsource (lib "eagle-import") (part "PINHD-1X6B"))
    )
    (comp (ref "JP14")
      (value "DIGITAL_1")
      (footprint "eagle-import:1X08-BIG")
      (libsource (lib "eagle-import") (part "PINHD-1X8BIG"))
    )
    (comp (ref "JP15")
      (value "DIGITAL_2")
      (footprint "eagle-import:1X10-BIG")
      (libsource (lib "eagle-import") (part "PINHD-1X10"))
    )
  )
  (nets
    (net (code "1") (name "+1.8V") (class "Default")
      (node (ref "C11") (pin "2") (pinfunction "2_2") (pintype "passive"))
      (node (ref "C26") (pin "1") (pinfunction "1_1") (pintype "passive"))
      (node (ref "C27") (pin "2") (pinfunction "2_2") (pintype "passive"))
      (node (ref "C29") (pin "2") (pinfunction "2_2") (pintype "passive"))
      (node (ref "J4") (pin "1") (pinfunction "1_1") (pintype "passive"))
      (node (ref "JP6") (pin "4") (pinfunction "4_4") (pintype "passive"))
      (node (ref "R46") (pin "2") (pinfunction "2_2") (pintype "passive"))
      (node (ref "R47") (pin "2") (pinfunction "2_2") (pintype "passive"))
      (node (ref "R6") (pin "2") (pinfunction "2_2") (pintype "passive"))
      (node (ref "SW1") (pin "2") (pinfunction "2_2") (pintype "passive"))
      (node (ref "U3") (pin "13") (pinfunction "VDD_13") (pintype "power_in"))
      (node (ref "U3") (pin "22") (pinfunction "NCS_22") (pintype "input"))
      (node (ref "U3") (pin "8") (pinfunction "VDDIO_8") (pintype "power_in"))
      (node (ref "U4") (pin "1") (pinfunction "VREF1_1") (pintype "bidirectional"))
      (node (ref "VR2") (pin "5") (pinfunction "VOUT_5") (pintype "power_in"))
    )
    (net (code "2") (name "+3V3") (class "Default")
      (node (ref "C9") (pin "1") (pinfunction "1_1") (pintype "passive"))
      (node (ref "J6") (pin "1") (pinfunction "1_1") (pintype "passive"))
      (node (ref "JP12") (pin "1") (pinfunction "1_1") (pintype "passive"))
      (node (ref "JP12") (pin "2") (pinfunction "2_2") (pintype "passive"))
      (node (ref "Q4") (pin "1") (pinfunction "G_1") (pintype "passive"))
      (node (ref "Q5") (pin "1") (pinfunction "G_1") (pintype "passive"))
      (node (ref "Q6") (pin "1") (pinfunction "G_1") (pintype "passive"))
      (node (ref "Q7") (pin "1") (pinfunction "G_1") (pintype "passive"))
      (node (ref "R3") (pin "2") (pinfunction "2_2") (pintype "passive"))
      (node (ref "R35") (pin "2") (pinfunction "2_2") (pintype "passive"))
      (node (ref "R36") (pin "2") (pinfunction "2_2") (pintype "passive"))
      (node (ref "R39") (pin "2") (pinfunction "2_2") (pintype "passive"))
      (node (ref "R40") (pin "2") (pinfunction "2_2") (pintype "passive"))
      (node (ref "VR1") (pin "5") (pinfunction "VOUT_5") (pintype "power_in"))
    )
    (net (code "3") (name "+3V3_FTDI") (class "Default")
      (node (ref "C16") (pin "1") (pinfunction "1_1") (pintype "passive"))
      (node (ref "R16") (pin "2") (pinfunction "2_2") (pintype "passive"))
      (node (ref "U2") (pin "17") (pinfunction "3V3OUT_17") (pintype "power_in"))
    )
    (net (code "4") (name "+5V") (class "Default")
      (node (ref "J13") (pin "1") (pinfunction "1_1") (pintype "passive"))
      (node (ref "J14") (pin "1") (pinfunction "1_1") (pintype "passive"))
      (node (ref "R23") (pin "2") (pinfunction "2_2") (pintype "passive"))
      (node (ref "R30") (pin "2") (pinfunction "2_2") (pintype "passive"))
    )
    (net (code "5") (name "+7.2V") (class "Default")
      (node (ref "C23") (pin "1") (pinfunction "1_1") (pintype "passive"))
      (node (ref "J11") (pin "1") (pinfunction "1_1") (pintype "passive"))
      (node (ref "J12") (pin "1") (pinfunction "1_1") (pintype "passive"))
      (node (ref "J16") (pin "1") (pinfunction "1_1") (pintype "passive"))
    )
    (net (code "6") (name "+VDD") (class "Default")
      (node (ref "C1") (pin "1") (pinfunction "1_1") (pintype "passive"))
      (node (ref "C17") (pin "1") (pinfunction "1_1") (pintype "passive"))
      (node (ref "C2") (pin "1") (pinfunction "1_1") (pintype "passive"))
      (node (ref "C24") (pin "2") (pinfunction "2_2") (pintype "passive"))
      (node (ref "C25") (pin "1") (pinfunction "1_1") (pintype "passive"))
      (node (ref "C3") (pin "1") (pinfunction "1_1") (pintype "passive"))
      (node (ref "C4") (pin "1") (pinfunction "1_1") (pintype "passive"))
      (node (ref "C5") (pin "1") (pinfunction "1_1") (pintype "passive"))
      (node (ref "C6") (pin "1") (pinfunction "1_1") (pintype "passive"))
      (node (ref "C7") (pin "1") (pinfunction "1_1") (pintype "passive"))
      (node (ref "C8") (pin "1") (pinfunction "1_1") (pintype "passive"))
      (node (ref "IC1") (pin "5") (pinfunction "VDD_5") (pintype "power_in"))
      (node (ref "J10") (pin "1") (pinfunction "1_1") (pintype "passive"))
      (node (ref "J15") (pin "1") (pinfunction "1_1") (pintype "passive"))
      (node (ref "J17") (pin "1") (pinfunction "1_1") (pintype "passive"))
      (node (ref "J18") (pin "1") (pinfunction "1_1") (pintype "passive"))
      (node (ref "J2") (pin "1") (pinfunction "1_1") (pintype "passive"))
      (node (ref "J20") (pin "1") (pinfunction "1_1") (pintype "passive"))
      (node (ref "J22") (pin "1") (pinfunction "1_1") (pintype "passive"))
      (node (ref "J3") (pin "1") (pinfunction "1_1") (pintype "passive"))
      (node (ref "J5") (pin "1") (pinfunction "1_1") (pintype "passive"))
      (node (ref "J7") (pin "1") (pinfunction "1_1") (pintype "passive"))
      (node (ref "J8") (pin "1") (pinfunction "1_1") (pintype "passive"))
      (node (ref "J9") (pin "1") (pinfunction "1_1") (pintype "passive"))
      (node (ref "JP6") (pin "1") (pinfunction "1_1") (pintype "passive"))
      (node (ref "JP6") (pin "2") (pinfunction "2_2") (pintype "passive"))
      (node (ref "JP6") (pin "3") (pinfunction "3_3") (pintype "passive"))
      (node (ref "Q3") (pin "3") (pinfunction "D_3") (pintype "passive"))
      (node (ref "R10") (pin "2") (pinfunction "2_2") (pintype "passive"))
      (node (ref "R11") (pin "2") (pinfunction "2_2") (pintype "passive"))
      (node (ref "R15") (pin "2") (pinfunction "2_2") (pintype "passive"))
      (node (ref "R18") (pin "2") (pinfunction "2_2") (pintype "passive"))
      (node (ref "R21") (pin "2") (pinfunction "2_2") (pintype "passive"))
      (node (ref "R22") (pin "2") (pinfunction "2_2") (pintype "passive"))
      (node (ref "R24") (pin "2") (pinfunction "2_2") (pintype "passive"))
      (node (ref "R26") (pin "2") (pinfunction "2_2") (pintype "passive"))
      (node (ref "R28") (pin "2") (pinfunction "2_2") (pintype "passive"))
      (node (ref "R29") (pin "2") (pinfunction "2_2") (pintype "passive"))
      (node (ref "R33") (pin "2") (pinfunction "2_2") (pintype "passive"))
      (node (ref "R34") (pin "2") (pinfunction "2_2") (pintype "passive"))
      (node (ref "R37") (pin "2") (pinfunction "2_2") (pintype "passive"))
      (node (ref "R38") (pin "2") (pinfunction "2_2") (pintype "passive"))
      (node (ref "R4") (pin "2") (pinfunction "2_2") (pintype "passive"))
      (node (ref "R41") (pin "2") (pinfunction "2_2") (pintype "passive"))
      (node (ref "R43") (pin "2") (pinfunction "2_2") (pintype "passive"))
      (node (ref "R44") (pin "2") (pinfunction "2_2") (pintype "passive"))
      (node (ref "R48") (pin "2") (pinfunction "2_2") (pintype "passive"))
      (node (ref "R49") (pin "2") (pinfunction "2_2") (pintype "passive"))
      (node (ref "R5") (pin "2") (pinfunction "2_2") (pintype "passive"))
      (node (ref "R7") (pin "2") (pinfunction "2_2") (pintype "passive"))
      (node (ref "R9") (pin "2") (pinfunction "2_2") (pintype "passive"))
      (node (ref "U$1") (pin "10") (pinfunction "VDD_10") (pintype "power_in"))
      (node (ref "U$1") (pin "11") (pinfunction "VDDA_11") (pintype "power_in"))
      (node (ref "U$1") (pin "12") (pinfunction "VREFH_12") (pintype "power_in"))
      (node (ref "U$1") (pin "38") (pinfunction "VDD1_38") (pintype "power_in"))
      (node (ref "U$1") (pin "61") (pinfunction "VDD2_61") (pintype "power_in"))
      (node (ref "U$1") (pin "87") (pinfunction "VDD3_87") (pintype "power_in"))
      (node (ref "U$12") (pin "1") (pinfunction "VCC_1") (pintype "power_in"))
      (node (ref "VR1") (pin "1") (pinfunction "VIN_1") (pintype "power_in"))
      (node (ref "VR1") (pin "3") (pinfunction "EN_3") (pintype "input"))
      (node (ref "VR2") (pin "1") (pinfunction "VIN_1") (pintype "power_in"))
      (node (ref "VR2") (pin "3") (pinfunction "EN_3") (pintype "input"))
    )
    (net (code "7") (name "+VUSB") (class "Default")
      (node (ref "C14") (pin "1") (pinfunction "1_1") (pintype "passive"))
      (node (ref "C15") (pin "1") (pinfunction "1_1") (pintype "passive"))
      (node (ref "FB1") (pin "2") (pinfunction "P$2_2") (pintype "passive"))
      (node (ref "R12") (pin "2") (pinfunction "2_2") (pintype "passive"))
      (node (ref "R13") (pin "2") (pinfunction "2_2") (pintype "passive"))
      (node (ref "R14") (pin "1") (pinfunction "1_1") (pintype "passive"))
      (node (ref "U2") (pin "20") (pinfunction "VCC_20") (pintype "power_in"))
      (node (ref "U2") (pin "4") (pinfunction "VCCIO_4") (pintype "power_in"))
    )
    (net (code "8") (name "3V3_SPI0_MISO") (class "Default")
      (node (ref "J6") (pin "4") (pinfunction "4_4") (pintype "passive"))
      (node (ref "Q5") (pin "2") (pinfunction "S_2") (pintype "passive"))
      (node (ref "R36") (pin "1") (pinfunction "1_1") (pintype "passive"))
    )
    (net (code "9") (name "3V3_SPI0_MOSI") (class "Default")
      (node (ref "J6") (pin "5") (pinfunction "5_5") (pintype "passive"))
      (node (ref "Q6") (pin "2") (pinfunction "S_2") (pintype "passive"))
      (node (ref "R39") (pin "1") (pinfunction "1_1") (pintype "passive"))
    )
    (net (code "10") (name "3V3_SPI0_PCS0") (class "Default")
      (node (ref "J6") (pin "6") (pinfunction "6_6") (pintype "passive"))
      (node (ref "Q7") (pin "2") (pinfunction "S_2") (pintype "passive"))
      (node (ref "R40") (pin "1") (pinfunction "1_1") (pintype "passive"))
    )
    (net (code "11") (name "3V3_SPI0_SCK") (class "Default")
      (node (ref "J6") (pin "3") (pinfunction "3_3") (pintype "passive"))
      (node (ref "Q4") (pin "2") (pinfunction "S_2") (pintype "passive"))
      (node (ref "R35") (pin "1") (pinfunction "1_1") (pintype "passive"))
    )
    (net (code "12") (name "ACMP0_IN3") (class "Default")
      (node (ref "JP11") (pin "4") (pinfunction "4_4") (pintype "passive"))
      (node (ref "U$1") (pin "26") (pinfunction "PTE8_26") (pintype "bidirectional"))
    )
    (net (code "13") (name "ACMP1_OUT") (class "Default")
      (node (ref "JP11") (pin "8") (pinfunction "8_8") (pintype "passive"))
      (node (ref "U$1") (pin "27") (pinfunction "PTB5_27") (pintype "bidirectional"))
    )
    (net (code "14") (name "ACMP2_IN0") (class "Default")
      (node (ref "JP11") (pin "2") (pinfunction "2_2") (pintype "passive"))
      (node (ref "U$1") (pin "21") (pinfunction "PTD16_21") (pintype "bidirectional"))
    )
    (net (code "15") (name "ACMP2_IN1") (class "Default")
      (node (ref "JP11") (pin "3") (pinfunction "3_3") (pintype "passive"))
      (node (ref "U$1") (pin "22") (pinfunction "PTD15_22") (pintype "bidirectional"))
    )
    (net (code "16") (name "ACMP2_IN3_{slash}_FTM0_FLT1") (class "Default")
      (node (ref "JP11") (pin "1") (pinfunction "1_1") (pintype "passive"))
      (node (ref "U$1") (pin "17") (pinfunction "PTE14_17") (pintype "bidirectional"))
    )
    (net (code "17") (name "ADC0_SE1_{slash}_ACMP0_IN1_{slash}_FTM1_CH1") (class "Default")
      (node (ref "JP9") (pin "8") (pinfunction "8_8") (pintype "passive"))
      (node (ref "U$1") (pin "78") (pinfunction "PTA1_78") (pintype "bidirectional"))
    )
    (net (code "18") (name "ADC0_SE5_{slash}_PTB1") (class "Default")
      (node (ref "JP5") (pin "2") (pinfunction "2_2") (pintype "passive"))
      (node (ref "U$1") (pin "53") (pinfunction "PTB1_53") (pintype "bidirectional"))
    )
    (net (code "19") (name "ADC0_SE10_{slash}_ACMP0_IN5") (class "Default")
      (node (ref "JP7") (pin "1") (pinfunction "1_1") (pintype "passive"))
      (node (ref "Q1") (pin "3") (pinfunction "D_3") (pintype "passive"))
      (node (ref "R6") (pin "1") (pinfunction "1_1") (pintype "passive"))
      (node (ref "U$1") (pin "30") (pinfunction "PTC2_30") (pintype "bidirectional"))
    )
    (net (code "20") (name "ADC0_SE11_{slash}_ACMP0_IN4") (class "Default")
      (node (ref "JP11") (pin "6") (pinfunction "6_6") (pintype "passive"))
      (node (ref "U$1") (pin "29") (pinfunction "PTC3_29") (pintype "bidirectional"))
    )
    (net (code "21") (name "ADC0_SE14_{slash}_PTC16") (class "Default")
      (node (ref "JP7") (pin "3") (pinfunction "3_3") (pintype "passive"))
      (node (ref "U$1") (pin "44") (pinfunction "PTC16_44") (pintype "bidirectional"))
      (node (ref "U3") (pin "11") (pinfunction "FSYNC_11") (pintype "input"))
    )
    (net (code "22") (name "ADC0_SE15_{slash}_PTC17") (class "Default")
      (node (ref "JP7") (pin "2") (pinfunction "2_2") (pintype "passive"))
      (node (ref "R30") (pin "1") (pinfunction "1_1") (pintype "passive"))
      (node (ref "R31") (pin "2") (pinfunction "2_2") (pintype "passive"))
      (node (ref "U$1") (pin "43") (pinfunction "PTC17_43") (pintype "bidirectional"))
    )
    (net (code "23") (name "ADC1_SE2_{slash}_FTM3_CH4") (class "Default")
      (node (ref "JP9") (pin "3") (pinfunction "3_3") (pintype "passive"))
      (node (ref "U$1") (pin "71") (pinfunction "PTD2_71") (pintype "bidirectional"))
    )
    (net (code "24") (name "ADC1_SE3_{slash}_FTM3_CH5_{slash}_NMI_B") (class "Default")
      (node (ref "JP9") (pin "2") (pinfunction "2_2") (pintype "passive"))
      (node (ref "U$1") (pin "70") (pinfunction "PTD3_70") (pintype "bidirectional"))
    )
    (net (code "25") (name "ADC1_SE6_{slash}_ACMP1_IN6_{slash}_FTM0_FLT3") (class "Default")
      (node (ref "JP9") (pin "1") (pinfunction "1_1") (pintype "passive"))
      (node (ref "U$1") (pin "69") (pinfunction "PTD4_69") (pintype "bidirectional"))
    )
    (net (code "26") (name "ADC2_SE8_{slash}_FTM3_CH3") (class "Default")
      (node (ref "JP9") (pin "4") (pinfunction "4_4") (pintype "passive"))
      (node (ref "U$1") (pin "74") (pinfunction "PTB11_74") (pintype "bidirectional"))
    )
    (net (code "27") (name "ADC2_SE9_{slash}_FTM3_CH2") (class "Default")
      (node (ref "JP9") (pin "5") (pinfunction "5_5") (pintype "passive"))
      (node (ref "U$1") (pin "75") (pinfunction "PTB10_75") (pintype "bidirectional"))
    )
    (net (code "28") (name "ADC2_SE10_{slash}_FTM3_CH1") (class "Default")
      (node (ref "JP9") (pin "6") (pinfunction "6_6") (pintype "passive"))
      (node (ref "U$1") (pin "76") (pinfunction "PTB9_76") (pintype "bidirectional"))
    )
    (net (code "29") (name "ADC2_SE11_{slash}_FTM3_CH0") (class "Default")
      (node (ref "JP9") (pin "7") (pinfunction "7_7") (pintype "passive"))
      (node (ref "U$1") (pin "77") (pinfunction "PTB8_77") (pintype "bidirectional"))
    )
    (net (code "30") (name "CLK_OUT_{slash}_FTM2_CH5") (class "Default")
      (node (ref "JP15") (pin "4") (pinfunction "4_4") (pintype "passive"))
      (node (ref "U$1") (pin "24") (pinfunction "PTD14_24") (pintype "bidirectional"))
    )
    (net (code "31") (name "D+") (class "Default")
      (node (ref "CN1") (pin "3") (pinfunction "D+_3") (pintype "bidirectional"))
      (node (ref "L2") (pin "1") (pinfunction "1_1") (pintype "passive"))
    )
    (net (code "32") (name "D-") (class "Default")
      (node (ref "CN1") (pin "2") (pinfunction "D-_2") (pintype "bidirectional"))
      (node (ref "L2") (pin "4") (pinfunction "4_4") (pintype "passive"))
    )
    (net (code "33") (name "DAC0_OUT") (class "Default")
      (node (ref "JP15") (pin "3") (pinfunction "3_3") (pintype "passive"))
      (node (ref "U$1") (pin "23") (pinfunction "PTE9_23") (pintype "bidirectional"))
    )
    (net (code "34") (name "DIGITAL_FIVE") (class "Default")
      (node (ref "JP1") (pin "1") (pinfunction "1_1") (pintype "passive"))
      (node (ref "JP13") (pin "5") (pinfunction "5_5") (pintype "passive"))
    )
    (net (code "35") (name "DIGITAL_FOUR") (class "Default")
      (node (ref "JP13") (pin "4") (pinfunction "4_4") (pintype "passive"))
      (node (ref "JP2") (pin "1") (pinfunction "1_1") (pintype "passive"))
    )
    (net (code "36") (name "DIGITAL_ONE") (class "Default")
      (node (ref "JP13") (pin "1") (pinfunction "1_1") (pintype "passive"))
      (node (ref "JP5") (pin "3") (pinfunction "3_3") (pintype "passive"))
    )
    (net (code "37") (name "DIGITAL_THREE") (class "Default")
      (node (ref "JP13") (pin "3") (pinfunction "3_3") (pintype "passive"))
      (node (ref "JP3") (pin "3") (pinfunction "3_3") (pintype "passive"))
    )
    (net (code "38") (name "DIGITAL_TWO") (class "Default")
      (node (ref "JP13") (pin "2") (pinfunction "2_2") (pintype "passive"))
      (node (ref "JP4") (pin "3") (pinfunction "3_3") (pintype "passive"))
    )
    (net (code "39") (name "FTM0_CH0_{slash}_ADC1_SE7") (class "Default")
      (node (ref "J11") (pin "2") (pinfunction "2_2") (pintype "passive"))
      (node (ref "JP8") (pin "1") (pinfunction "1_1") (pintype "passive"))
      (node (ref "U$1") (pin "68") (pinfunction "PTB12_68") (pintype "bidirectional"))
    )
    (net (code "40") (name "FTM0_CH1_{slash}_ADC1_SE8") (class "Default")
      (node (ref "JP8") (pin "2") (pinfunction "2_2") (pintype "passive"))
      (node (ref "U$1") (pin "67") (pinfunction "PTB13_67") (pintype "bidirectional"))
    )
    (net (code "41") (name "FTM0_CH2_{slash}_ADC1_SE9") (class "Default")
      (node (ref "J12") (pin "2") (pinfunction "2_2") (pintype "passive"))
      (node (ref "JP8") (pin "3") (pinfunction "3_3") (pintype "passive"))
      (node (ref "U$1") (pin "66") (pinfunction "PTB14_66") (pintype "bidirectional"))
    )
    (net (code "42") (name "FTM0_CH3_{slash}_ADC1_SE14") (class "Default")
      (node (ref "JP8") (pin "4") (pinfunction "4_4") (pintype "passive"))
      (node (ref "U$1") (pin "65") (pinfunction "PTB15_65") (pintype "bidirectional"))
    )
    (net (code "43") (name "FTM0_CH4_{slash}_ADC1_SE15") (class "Default")
      (node (ref "JP8") (pin "5") (pinfunction "5_5") (pintype "passive"))
      (node (ref "U$1") (pin "64") (pinfunction "PTB16_64") (pintype "bidirectional"))
    )
    (net (code "44") (name "FTM0_CH5_{slash}_ADC2_SE3") (class "Default")
      (node (ref "JP8") (pin "6") (pinfunction "6_6") (pintype "passive"))
      (node (ref "U$1") (pin "63") (pinfunction "PTB17_63") (pintype "bidirectional"))
    )
    (net (code "45") (name "FTM0_CH6") (class "Default")
      (node (ref "J13") (pin "2") (pinfunction "2_2") (pintype "passive"))
      (node (ref "JP8") (pin "7") (pinfunction "7_7") (pintype "passive"))
      (node (ref "U$1") (pin "62") (pinfunction "PTA17_62") (pintype "bidirectional"))
    )
    (net (code "46") (name "FTM0_CH7_{slash}_ADC2_SE2") (class "Default")
      (node (ref "JP8") (pin "8") (pinfunction "8_8") (pintype "passive"))
      (node (ref "U$1") (pin "59") (pinfunction "PTE7_59") (pintype "bidirectional"))
    )
    (net (code "47") (name "FTM0_FLT0&2_{slash}_TRGMUX_IN6_{slash}_ACMP2_OUT") (class "Default")
      (node (ref "JP11") (pin "7") (pinfunction "7_7") (pintype "passive"))
      (node (ref "U$1") (pin "18") (pinfunction "PTE3_18") (pintype "bidirectional"))
    )
    (net (code "48") (name "FTM1_CH2_{slash}_ADC0_SE12") (class "Default")
      (node (ref "J21") (pin "2") (pinfunction "2_2") (pintype "passive"))
      (node (ref "U$1") (pin "46") (pinfunction "PTC14_46") (pintype "bidirectional"))
    )
    (net (code "49") (name "FTM1_CH3_{slash}_ADC0_SE13") (class "Default")
      (node (ref "J21") (pin "3") (pinfunction "3_3") (pintype "passive"))
      (node (ref "U$1") (pin "45") (pinfunction "PTC15_45") (pintype "bidirectional"))
    )
    (net (code "50") (name "FTM1_CH6_{slash}_ADC0_SE8") (class "Default")
      (node (ref "J21") (pin "4") (pinfunction "4_4") (pintype "passive"))
      (node (ref "U$1") (pin "40") (pinfunction "PTC0_40") (pintype "bidirectional"))
    )
    (net (code "51") (name "FTM1_CH7_{slash}_ADC0_SE9") (class "Default")
      (node (ref "J21") (pin "5") (pinfunction "5_5") (pintype "passive"))
      (node (ref "U$1") (pin "39") (pinfunction "PTC1_39") (pintype "bidirectional"))
    )
    (net (code "52") (name "FTM1_QD_PHA_{slash}_ADC0_SE7") (class "Default")
      (node (ref "J20") (pin "2") (pinfunction "2_2") (pintype "passive"))
      (node (ref "U$1") (pin "47") (pinfunction "PTB3_47") (pintype "bidirectional"))
    )
    (net (code "53") (name "FTM1_QD_PHB_{slash}_ADC0_SE6") (class "Default")
      (node (ref "J20") (pin "3") (pinfunction "3_3") (pintype "passive"))
      (node (ref "U$1") (pin "48") (pinfunction "PTB2_48") (pintype "bidirectional"))
    )
    (net (code "54") (name "FTM2_CH4_{slash}_FXIO_D4_{slash}_TRGMUX_OUT4") (class "Default")
      (node (ref "J22") (pin "3") (pinfunction "3_3") (pintype "passive"))
      (node (ref "JP10") (pin "5") (pinfunction "5_5") (pintype "passive"))
      (node (ref "U$1") (pin "6") (pinfunction "PTE10_6") (pintype "bidirectional"))
    )
    (net (code "55") (name "FTM2_CH6_{slash}_FXIO_D2_{slash}_TRGMUX_OUT6") (class "Default")
      (node (ref "J22") (pin "5") (pinfunction "5_5") (pintype "passive"))
      (node (ref "JP10") (pin "3") (pinfunction "3_3") (pintype "passive"))
      (node (ref "R41") (pin "1") (pinfunction "1_1") (pintype "passive"))
      (node (ref "U$1") (pin "2") (pinfunction "PTE15_2") (pintype "bidirectional"))
    )
    (net (code "56") (name "FTM2_CH7_{slash}_FXIO_D3_{slash}_TRGMUX_OUT7") (class "Default")
      (node (ref "J22") (pin "4") (pinfunction "4_4") (pintype "passive"))
      (node (ref "JP10") (pin "4") (pinfunction "4_4") (pintype "passive"))
      (node (ref "U$1") (pin "1") (pinfunction "PTE16_1") (pintype "bidirectional"))
    )
    (net (code "57") (name "FTM2_QD_PHA_{slash}_TCLK2") (class "Default")
      (node (ref "J15") (pin "2") (pinfunction "2_2") (pintype "passive"))
      (node (ref "U$1") (pin "8") (pinfunction "PTE5_8") (pintype "bidirectional"))
    )
    (net (code "58") (name "FTM2_QD_PHB_{slash}_BUSOUT") (class "Default")
      (node (ref "J15") (pin "3") (pinfunction "3_3") (pintype "passive"))
      (node (ref "U$1") (pin "9") (pinfunction "PTE4_9") (pintype "bidirectional"))
    )
    (net (code "59") (name "FXIO_D0_{slash}_ADC2_SE0") (class "Default")
      (node (ref "J17") (pin "3") (pinfunction "3_3") (pintype "passive"))
      (node (ref "J18") (pin "3") (pinfunction "3_3") (pintype "passive"))
      (node (ref "JP10") (pin "1") (pinfunction "1_1") (pintype "passive"))
      (node (ref "R28") (pin "1") (pinfunction "1_1") (pintype "passive"))
      (node (ref "U$1") (pin "4") (pinfunction "PTD0_4") (pintype "bidirectional"))
    )
    (net (code "60") (name "FXIO_D1_{slash}_ADC2_SE1") (class "Default")
      (node (ref "J17") (pin "4") (pinfunction "4_4") (pintype "passive"))
      (node (ref "J18") (pin "4") (pinfunction "4_4") (pintype "passive"))
      (node (ref "JP10") (pin "2") (pinfunction "2_2") (pintype "passive"))
      (node (ref "R29") (pin "1") (pinfunction "1_1") (pintype "passive"))
      (node (ref "U$1") (pin "3") (pinfunction "PTD1_3") (pintype "bidirectional"))
    )
    (net (code "61") (name "FXIO_D6_{slash}_PTA8") (class "Default")
      (node (ref "JP10") (pin "7") (pinfunction "7_7") (pintype "passive"))
      (node (ref "U$1") (pin "100") (pinfunction "PTA8_100") (pintype "bidirectional"))
    )
    (net (code "62") (name "FXIO_D7_{slash}_PTA9") (class "Default")
      (node (ref "JP10") (pin "8") (pinfunction "8_8") (pintype "passive"))
      (node (ref "U$1") (pin "99") (pinfunction "PTA9_99") (pintype "bidirectional"))
    )
    (net (code "63") (name "GND") (class "Default")
      (node (ref "C1") (pin "2") (pinfunction "2_2") (pintype "passive"))
      (node (ref "C11") (pin "1") (pinfunction "1_1") (pintype "passive"))
      (node (ref "C12") (pin "2") (pinfunction "2_2") (pintype "passive"))
      (node (ref "C13") (pin "2") (pinfunction "2_2") (pintype "passive"))
      (node (ref "C14") (pin "2") (pinfunction "2_2") (pintype "passive"))
      (node (ref "C15") (pin "2") (pinfunction "2_2") (pintype "passive"))
      (node (ref "C16") (pin "2") (pinfunction "2_2") (pintype "passive"))
      (node (ref "C17") (pin "2") (pinfunction "2_2") (pintype "passive"))
      (node (ref "C18") (pin "2") (pinfunction "2_2") (pintype "passive"))
      (node (ref "C19") (pin "2") (pinfunction "2_2") (pintype "passive"))
      (node (ref "C2") (pin "2") (pinfunction "2_2") (pintype "passive"))
      (node (ref "C20") (pin "2") (pinfunction "2_2") (pintype "passive"))
      (node (ref "C21") (pin "2") (pinfunction "2_2") (pintype "passive"))
      (node (ref "C22") (pin "2") (pinfunction "2_2") (pintype "passive"))
      (node (ref "C23") (pin "2") (pinfunction "2_2") (pintype "passive"))
      (node (ref "C24") (pin "1") (pinfunction "1_1") (pintype "passive"))
      (node (ref "C25") (pin "2") (pinfunction "2_2") (pintype "passive"))
      (node (ref "C26") (pin "2") (pinfunction "2_2") (pintype "passive"))
      (node (ref "C27") (pin "1") (pinfunction "1_1") (pintype "passive"))
      (node (ref "C28") (pin "1") (pinfunction "1_1") (pintype "passive"))
      (node (ref "C29") (pin "1") (pinfunction "1_1") (pintype "passive"))
      (node (ref "C3") (pin "2") (pinfunction "2_2") (pintype "passive"))
      (node (ref "C4") (pin "2") (pinfunction "2_2") (pintype "passive"))
      (node (ref "C5") (pin "2") (pinfunction "2_2") (pintype "passive"))
      (node (ref "C6") (pin "2") (pinfunction "2_2") (pintype "passive"))
      (node (ref "C7") (pin "2") (pinfunction "2_2") (pintype "passive"))
      (node (ref "C8") (pin "2") (pinfunction "2_2") (pintype "passive"))
      (node (ref "C9") (pin "2") (pinfunction "2_2") (pintype "passive"))
      (node (ref "CN1") (pin "5") (pinfunction "GND_5") (pintype "power_in"))
      (node (ref "CN1") (pin "GND1") (pinfunction "GND_GND1") (pintype "power_in"))
      (node (ref "CN1") (pin "GND2") (pinfunction "GND_GND2") (pintype "power_in"))
      (node (ref "D1") (pin "2") (pinfunction "C_2") (pintype "passive"))
      (node (ref "D2") (pin "2") (pinfunction "C_2") (pintype "passive"))
      (node (ref "D3") (pin "2") (pinfunction "C_2") (pintype "passive"))
      (node (ref "D4") (pin "2") (pinfunction "C_2") (pintype "passive"))
      (node (ref "D7") (pin "2") (pinfunction "C_2") (pintype "passive"))
      (node (ref "D8") (pin "2") (pinfunction "C_2") (pintype "passive"))
      (node (ref "DEBUG/RACE") (pin "1") (pinfunction "1_1") (pintype "passive"))
      (node (ref "IC1") (pin "3") (pinfunction "GND_3") (pintype "power_in"))
      (node (ref "J10") (pin "2") (pinfunction "2_2") (pintype "passive"))
      (node (ref "J11") (pin "3") (pinfunction "3_3") (pintype "passive"))
      (node (ref "J12") (pin "3") (pinfunction "3_3") (pintype "passive"))
      (node (ref "J13") (pin "3") (pinfunction "3_3") (pintype "passive"))
      (node (ref "J14") (pin "2") (pinfunction "2_2") (pintype "passive"))
      (node (ref "J15") (pin "4") (pinfunction "4_4") (pintype "passive"))
      (node (ref "J16") (pin "2") (pinfunction "2_2") (pintype "passive"))
      (node (ref "J17") (pin "2") (pinfunction "2_2") (pintype "passive"))
      (node (ref "J18") (pin "2") (pinfunction "2_2") (pintype "passive"))
      (node (ref "J2") (pin "2") (pinfunction "2_2") (pintype "passive"))
      (node (ref "J20") (pin "4") (pinfunction "4_4") (pintype "passive"))
      (node (ref "J21") (pin "1") (pinfunction "1_1") (pintype "passive"))
      (node (ref "J22") (pin "2") (pinfunction "2_2") (pintype "passive"))
      (node (ref "J3") (pin "2") (pinfunction "2_2") (pintype "passive"))
      (node (ref "J4") (pin "2") (pinfunction "2_2") (pintype "passive"))
      (node (ref "J5") (pin "2") (pinfunction "2_2") (pintype "passive"))
      (node (ref "J6") (pin "2") (pinfunction "2_2") (pintype "passive"))
      (node (ref "J7") (pin "2") (pinfunction "2_2") (pintype "passive"))
      (node (ref "J8") (pin "2") (pinfunction "2_2") (pintype "passive"))
      (node (ref "J9") (pin "2") (pinfunction "2_2") (pintype "passive"))
      (node (ref "JP12") (pin "3") (pinfunction "3_3") (pintype "passive"))
      (node (ref "JP13") (pin "6") (pinfunction "6_6") (pintype "passive"))
      (node (ref "JP15") (pin "10") (pinfunction "10_10") (pintype "passive"))
      (node (ref "JP6") (pin "5") (pinfunction "5_5") (pintype "passive"))
      (node (ref "JP6") (pin "6") (pinfunction "6_6") (pintype "passive"))
      (node (ref "JP6") (pin "7") (pinfunction "7_7") (pintype "passive"))
      (node (ref "JP6") (pin "8") (pinfunction "8_8") (pintype "passive"))
      (node (ref "Q1") (pin "2") (pinfunction "S_2") (pintype "passive"))
      (node (ref "Q8") (pin "2") (pinfunction "S_2") (pintype "passive"))
      (node (ref "R20") (pin "1") (pinfunction "1_1") (pintype "passive"))
      (node (ref "R25") (pin "1") (pinfunction "1_1") (pintype "passive"))
      (node (ref "R31") (pin "1") (pinfunction "1_1") (pintype "passive"))
      (node (ref "R32") (pin "1") (pinfunction "1_1") (pintype "passive"))
      (node (ref "RC/AUTO") (pin "1") (pinfunction "1_1") (pintype "passive"))
      (node (ref "S1") (pin "1") (pinfunction "0_1") (pintype "passive"))
      (node (ref "S1") (pin "2") (pinfunction "0_2") (pintype "passive"))
      (node (ref "S2") (pin "1") (pinfunction "0_1") (pintype "passive"))
      (node (ref "S2") (pin "2") (pinfunction "0_2") (pintype "passive"))
      (node (ref "U$1") (pin "13") (pinfunction "VREFL_13") (pintype "power_in"))
      (node (ref "U$1") (pin "14") (pinfunction "VSS_14") (pintype "power_in"))
      (node (ref "U$1") (pin "37") (pinfunction "VSS1_37") (pintype "power_in"))
      (node (ref "U$1") (pin "60") (pinfunction "VSS2_60") (pintype "power_in"))
      (node (ref "U$1") (pin "86") (pinfunction "VSS3_86") (pintype "power_in"))
      (node (ref "U$12") (pin "3") (pinfunction "GND_3") (pintype "power_in"))
      (node (ref "U$12") (pin "5") (pinfunction "GND2_5") (pintype "power_in"))
      (node (ref "U$12") (pin "7") (pinfunction "KEY_7") (pintype "bidirectional"))
      (node (ref "U$12") (pin "9") (pinfunction "GND_DCT_9") (pintype "power_in"))
      (node (ref "U2") (pin "18") (pinfunction "GND2_18") (pintype "power_in"))
      (node (ref "U2") (pin "21") (pinfunction "GND3_21") (pintype "power_in"))
      (node (ref "U2") (pin "25") (pinfunction "AGND_25") (pintype "power_in"))
      (node (ref "U2") (pin "26") (pinfunction "TEST_26") (pintype "input"))
      (node (ref "U2") (pin "7") (pinfunction "GND1_7") (pintype "power_in"))
      (node (ref "U3") (pin "18") (pinfunction "GND_18") (pintype "power_in"))
      (node (ref "U3") (pin "20") (pinfunction "RESV_20_20") (pintype "passive"))
      (node (ref "U3") (pin "25") (pinfunction "EXP_PAD_25") (pintype "power_in"))
      (node (ref "U4") (pin "4") (pinfunction "GND_4") (pintype "bidirectional"))
      (node (ref "VR1") (pin "2") (pinfunction "GND_2") (pintype "power_in"))
      (node (ref "VR2") (pin "2") (pinfunction "GND_2") (pintype "power_in"))
    )
    (net (code "64") (name "I2C0_SCL") (class "Default")
      (node (ref "J10") (pin "3") (pinfunction "3_3") (pintype "passive"))
      (node (ref "J2") (pin "3") (pinfunction "3_3") (pintype "passive"))
      (node (ref "J3") (pin "3") (pinfunction "3_3") (pintype "passive"))
      (node (ref "J9") (pin "3") (pinfunction "3_3") (pintype "passive"))
      (node (ref "R9") (pin "1") (pinfunction "1_1") (pintype "passive"))
      (node (ref "U$1") (pin "15") (pinfunction "PTB7_15") (pintype "bidirectional"))
    )
    (net (code "65") (name "I2C0_SDA") (class "Default")
      (node (ref "J10") (pin "4") (pinfunction "4_4") (pintype "passive"))
      (node (ref "J2") (pin "4") (pinfunction "4_4") (pintype "passive"))
      (node (ref "J3") (pin "4") (pinfunction "4_4") (pintype "passive"))
      (node (ref "J9") (pin "4") (pinfunction "4_4") (pintype "passive"))
      (node (ref "R10") (pin "1") (pinfunction "1_1") (pintype "passive"))
      (node (ref "U$1") (pin "16") (pinfunction "PTB6_16") (pintype "bidirectional"))
    )
    (net (code "66") (name "I2C1_1.8_SCL") (class "Default")
      (node (ref "J4") (pin "3") (pinfunction "3_3") (pintype "passive"))
      (node (ref "R46") (pin "1") (pinfunction "1_1") (pintype "passive"))
      (node (ref "U3") (pin "23") (pinfunction "SCL/SCLK_23") (pintype "input"))
      (node (ref "U4") (pin "2") (pinfunction "SCL1_2") (pintype "bidirectional"))
    )
    (net (code "67") (name "I2C1_1.8_SDA") (class "Default")
      (node (ref "J4") (pin "4") (pinfunction "4_4") (pintype "passive"))
      (node (ref "R47") (pin "1") (pinfunction "1_1") (pintype "passive"))
      (node (ref "U3") (pin "24") (pinfunction "SDA/SDI_24") (pintype "bidirectional"))
      (node (ref "U4") (pin "3") (pinfunction "SDA1_3") (pintype "bidirectional"))
    )
    (net (code "68") (name "I2C1_SDA") (class "Default")
      (node (ref "R49") (pin "1") (pinfunction "1_1") (pintype "passive"))
      (node (ref "U$1") (pin "42") (pinfunction "PTD8_42") (pintype "bidirectional"))
      (node (ref "U4") (pin "5") (pinfunction "SDA2_5") (pintype "bidirectional"))
    )
    (net (code "69") (name "I2C1__SCL") (class "Default")
      (node (ref "R48") (pin "1") (pinfunction "1_1") (pintype "passive"))
      (node (ref "U$1") (pin "41") (pinfunction "PTD9_41") (pintype "bidirectional"))
      (node (ref "U4") (pin "6") (pinfunction "SCL2_6") (pintype "bidirectional"))
    )
    (net (code "70") (name "JTAG_TCLK{slash}SWD_CLK") (class "Default")
      (node (ref "R20") (pin "2") (pinfunction "2_2") (pintype "passive"))
      (node (ref "U$1") (pin "96") (pinfunction "PTC4_96") (pintype "bidirectional"))
      (node (ref "U$12") (pin "4") (pinfunction "SWDCLK/TCK_4") (pintype "bidirectional"))
    )
    (net (code "71") (name "JTAG_TDI") (class "Default")
      (node (ref "U$1") (pin "95") (pinfunction "PTC5_95") (pintype "bidirectional"))
      (node (ref "U$12") (pin "8") (pinfunction "NC/TDI_8") (pintype "bidirectional"))
    )
    (net (code "72") (name "JTAG_TDO{slash}SWO") (class "Default")
      (node (ref "U$1") (pin "92") (pinfunction "PTA10_92") (pintype "bidirectional"))
      (node (ref "U$12") (pin "6") (pinfunction "SWO/TDO_6") (pintype "bidirectional"))
    )
    (net (code "73") (name "JTAG_TMS{slash}SWD_DIO") (class "Default")
      (node (ref "R11") (pin "1") (pinfunction "1_1") (pintype "passive"))
      (node (ref "U$1") (pin "98") (pinfunction "PTA4_98") (pintype "bidirectional"))
      (node (ref "U$12") (pin "2") (pinfunction "SWDIO/TMS_2") (pintype "bidirectional"))
    )
    (net (code "74") (name "JTAG_TRST_B") (class "Default")
      (node (ref "C18") (pin "1") (pinfunction "1_1") (pintype "passive"))
      (node (ref "R21") (pin "1") (pinfunction "1_1") (pintype "passive"))
      (node (ref "R27") (pin "2") (pinfunction "2_2") (pintype "passive"))
      (node (ref "U$1") (pin "97") (pinfunction "PTA5_97") (pintype "bidirectional"))
      (node (ref "U$12") (pin "10") (pinfunction "/R/E/S/E/T_10") (pintype "bidirectional"))
    )
    (net (code "75") (name "Net-(C20-Pad1)") (class "Default")
      (node (ref "C20") (pin "1") (pinfunction "1_1") (pintype "passive"))
      (node (ref "JP5") (pin "1") (pinfunction "1_1") (pintype "passive"))
      (node (ref "R22") (pin "1") (pinfunction "1_1") (pintype "passive"))
      (node (ref "S1") (pin "3") (pinfunction "1_3") (pintype "passive"))
      (node (ref "S1") (pin "4") (pinfunction "1_4") (pintype "passive"))
    )
    (net (code "76") (name "Net-(C21-Pad1)") (class "Default")
      (node (ref "C21") (pin "1") (pinfunction "1_1") (pintype "passive"))
      (node (ref "JP4") (pin "1") (pinfunction "1_1") (pintype "passive"))
      (node (ref "R18") (pin "1") (pinfunction "1_1") (pintype "passive"))
      (node (ref "RC/AUTO") (pin "2") (pinfunction "2_2") (pintype "passive"))
    )
    (net (code "77") (name "Net-(C22-Pad1)") (class "Default")
      (node (ref "C22") (pin "1") (pinfunction "1_1") (pintype "passive"))
      (node (ref "DEBUG/RACE") (pin "2") (pinfunction "2_2") (pintype "passive"))
      (node (ref "JP3") (pin "1") (pinfunction "1_1") (pintype "passive"))
      (node (ref "R15") (pin "1") (pinfunction "1_1") (pintype "passive"))
    )
    (net (code "78") (name "Net-(D1-A)") (class "Default")
      (node (ref "D1") (pin "1") (pinfunction "A_1") (pintype "passive"))
      (node (ref "R1") (pin "1") (pinfunction "1_1") (pintype "passive"))
    )
    (net (code "79") (name "Net-(D2-A)") (class "Default")
      (node (ref "D2") (pin "1") (pinfunction "A_1") (pintype "passive"))
      (node (ref "R2") (pin "1") (pinfunction "1_1") (pintype "passive"))
    )
    (net (code "80") (name "Net-(D3-A)") (class "Default")
      (node (ref "D3") (pin "1") (pinfunction "A_1") (pintype "passive"))
      (node (ref "R3") (pin "1") (pinfunction "1_1") (pintype "passive"))
    )
    (net (code "81") (name "Net-(D4-A)") (class "Default")
      (node (ref "D4") (pin "1") (pinfunction "A_1") (pintype "passive"))
      (node (ref "R4") (pin "1") (pinfunction "1_1") (pintype "passive"))
    )
    (net (code "82") (name "Net-(D5-A)") (class "Default")
      (node (ref "D5") (pin "1") (pinfunction "A_1") (pintype "passive"))
      (node (ref "R12") (pin "1") (pinfunction "1_1") (pintype "passive"))
    )
    (net (code "83") (name "Net-(D5-C)") (class "Default")
      (node (ref "D5") (pin "2") (pinfunction "C_2") (pintype "passive"))
      (node (ref "U2") (pin "23") (pinfunction "TXLED_23") (pintype "bidirectional"))
    )
    (net (code "84") (name "Net-(D6-A)") (class "Default")
      (node (ref "D6") (pin "1") (pinfunction "A_1") (pintype "passive"))
      (node (ref "R13") (pin "1") (pinfunction "1_1") (pintype "passive"))
    )
    (net (code "85") (name "Net-(D6-C)") (class "Default")
      (node (ref "D6") (pin "2") (pinfunction "C_2") (pintype "passive"))
      (node (ref "U2") (pin "22") (pinfunction "RXLED_22") (pintype "bidirectional"))
    )
    (net (code "86") (name "Net-(D7-A)") (class "Default")
      (node (ref "D7") (pin "1") (pinfunction "A_1") (pintype "passive"))
      (node (ref "R16") (pin "1") (pinfunction "1_1") (pintype "passive"))
    )
    (net (code "87") (name "Net-(D8-A)") (class "Default")
      (node (ref "D8") (pin "1") (pinfunction "A_1") (pintype "passive"))
      (node (ref "R14") (pin "2") (pinfunction "2_2") (pintype "passive"))
    )
    (net (code "88") (name "Net-(IC1-A)") (class "Default")
      (node (ref "IC1") (pin "2") (pinfunction "A_2") (pintype "input"))
      (node (ref "Q8") (pin "3") (pinfunction "D_3") (pintype "passive"))
      (node (ref "R44") (pin "1") (pinfunction "1_1") (pintype "passive"))
    )
    (net (code "89") (name "Net-(IC1-OUT)") (class "Default")
      (node (ref "IC1") (pin "4") (pinfunction "OUT_4") (pintype "output"))
      (node (ref "Q3") (pin "1") (pinfunction "G_1") (pintype "passive"))
      (node (ref "R43") (pin "1") (pinfunction "1_1") (pintype "passive"))
    )
    (net (code "90") (name "Net-(J21-Pad6)") (class "Default")
      (node (ref "J21") (pin "6") (pinfunction "6_6") (pintype "passive"))
      (node (ref "R7") (pin "1") (pinfunction "1_1") (pintype "passive"))
    )
    (net (code "91") (name "Net-(JP1-Pad3)") (class "Default")
      (node (ref "JP1") (pin "3") (pinfunction "3_3") (pintype "passive"))
      (node (ref "R2") (pin "2") (pinfunction "2_2") (pintype "passive"))
    )
    (net (code "92") (name "Net-(JP2-Pad3)") (class "Default")
      (node (ref "JP2") (pin "3") (pinfunction "3_3") (pintype "passive"))
      (node (ref "R1") (pin "2") (pinfunction "2_2") (pintype "passive"))
    )
    (net (code "93") (name "Net-(L1-Pad1)") (class "Default")
      (node (ref "L1") (pin "1") (pinfunction "1_1") (pintype "passive"))
      (node (ref "R23") (pin "1") (pinfunction "1_1") (pintype "passive"))
    )
    (net (code "94") (name "Net-(Q1-G)") (class "Default")
      (node (ref "Q1") (pin "1") (pinfunction "G_1") (pintype "passive"))
      (node (ref "U3") (pin "12") (pinfunction "INT1_12") (pintype "output"))
    )
    (net (code "95") (name "Net-(Q3-S)") (class "Default")
      (node (ref "C13") (pin "1") (pinfunction "1_1") (pintype "passive"))
      (node (ref "L1") (pin "2") (pinfunction "2_2") (pintype "passive"))
      (node (ref "Q3") (pin "2") (pinfunction "S_2") (pintype "passive"))
    )
    (net (code "96") (name "Net-(Q8-G)") (class "Default")
      (node (ref "J19") (pin "1") (pinfunction "1_1") (pintype "passive"))
      (node (ref "Q8") (pin "1") (pinfunction "G_1") (pintype "passive"))
    )
    (net (code "97") (name "Net-(R24-Pad1)") (class "Default")
      (node (ref "R24") (pin "1") (pinfunction "1_1") (pintype "passive"))
      (node (ref "R27") (pin "1") (pinfunction "1_1") (pintype "passive"))
      (node (ref "S2") (pin "3") (pinfunction "1_3") (pintype "passive"))
      (node (ref "S2") (pin "4") (pinfunction "1_4") (pintype "passive"))
    )
    (net (code "98") (name "Net-(S3-O)") (class "Default")
      (node (ref "R25") (pin "2") (pinfunction "2_2") (pintype "passive"))
      (node (ref "S3") (pin "1") (pinfunction "O_1") (pintype "passive"))
    )
    (net (code "99") (name "Net-(S3-S)") (class "Default")
      (node (ref "R26") (pin "1") (pinfunction "1_1") (pintype "passive"))
      (node (ref "S3") (pin "3") (pinfunction "S_3") (pintype "passive"))
    )
    (net (code "100") (name "Net-(U2-USB+)") (class "Default")
      (node (ref "L2") (pin "2") (pinfunction "2_2") (pintype "passive"))
      (node (ref "U2") (pin "15") (pinfunction "USB+_15") (pintype "bidirectional"))
    )
    (net (code "101") (name "Net-(U2-USB-)") (class "Default")
      (node (ref "L2") (pin "3") (pinfunction "3_3") (pintype "passive"))
      (node (ref "U2") (pin "16") (pinfunction "USB-_16") (pintype "bidirectional"))
    )
    (net (code "102") (name "Net-(U3-AD0{slash}SDO)") (class "Default")
      (node (ref "R32") (pin "2") (pinfunction "2_2") (pintype "passive"))
      (node (ref "SW1") (pin "1") (pinfunction "1_1") (pintype "passive"))
      (node (ref "U3") (pin "9") (pinfunction "AD0/SDO_9") (pintype "output"))
    )
    (net (code "103") (name "Net-(U3-REGOUT)") (class "Default")
      (node (ref "C12") (pin "1") (pinfunction "1_1") (pintype "passive"))
      (node (ref "U3") (pin "10") (pinfunction "REGOUT_10") (pintype "output"))
    )
    (net (code "104") (name "Net-(U4-EN)") (class "Default")
      (node (ref "C28") (pin "2") (pinfunction "2_2") (pintype "passive"))
      (node (ref "R5") (pin "1") (pinfunction "1_1") (pintype "passive"))
      (node (ref "U4") (pin "7") (pinfunction "VREF2_7") (pintype "bidirectional"))
      (node (ref "U4") (pin "8") (pinfunction "EN_8") (pintype "bidirectional"))
    )
    (net (code "105") (name "POWER_SHUT_DOWN") (class "Default")
      (node (ref "C19") (pin "1") (pinfunction "1_1") (pintype "passive"))
      (node (ref "IC1") (pin "1") (pinfunction "B_1") (pintype "input"))
      (node (ref "S3") (pin "2") (pinfunction "P_2") (pintype "passive"))
    )
    (net (code "106") (name "PTA0_{slash}_ADC0_SE0") (class "Default")
      (node (ref "JP14") (pin "1") (pinfunction "1_1") (pintype "passive"))
      (node (ref "U$1") (pin "79") (pinfunction "PTA0_79") (pintype "bidirectional"))
    )
    (net (code "107") (name "PTA11_{slash}_FTM1_CH5") (class "Default")
      (node (ref "JP15") (pin "1") (pinfunction "1_1") (pintype "passive"))
      (node (ref "U$1") (pin "91") (pinfunction "PTA11_91") (pintype "bidirectional"))
    )
    (net (code "108") (name "PTA12_{slash}_ADC2_SE5") (class "Default")
      (node (ref "JP14") (pin "8") (pinfunction "8_8") (pintype "passive"))
      (node (ref "U$1") (pin "90") (pinfunction "PTA12_90") (pintype "bidirectional"))
    )
    (net (code "109") (name "PTA13_{slash}_ADC2_SE4") (class "Default")
      (node (ref "JP14") (pin "7") (pinfunction "7_7") (pintype "passive"))
      (node (ref "U$1") (pin "89") (pinfunction "PTA13_89") (pintype "bidirectional"))
    )
    (net (code "110") (name "PTA14") (class "Default")
      (node (ref "JP14") (pin "6") (pinfunction "6_6") (pintype "passive"))
      (node (ref "U$1") (pin "88") (pinfunction "PTA14_88") (pintype "bidirectional"))
    )
    (net (code "111") (name "PTA16_{slash}_ADC1_SE13") (class "Default")
      (node (ref "JP14") (pin "4") (pinfunction "4_4") (pintype "passive"))
      (node (ref "U$1") (pin "82") (pinfunction "PTA16_82") (pintype "bidirectional"))
    )
    (net (code "112") (name "PTB4_{slash}_ACMP1_IN2") (class "Default")
      (node (ref "JP11") (pin "5") (pinfunction "5_5") (pintype "passive"))
      (node (ref "U$1") (pin "28") (pinfunction "PTB4_28") (pintype "bidirectional"))
    )
    (net (code "113") (name "PTC6_{slash}_ADC1_SE4") (class "Default")
      (node (ref "JP14") (pin "3") (pinfunction "3_3") (pintype "passive"))
      (node (ref "U$1") (pin "81") (pinfunction "PTC6_81") (pintype "bidirectional"))
    )
    (net (code "114") (name "PTC7_{slash}_ADC1_SE5") (class "Default")
      (node (ref "JP14") (pin "2") (pinfunction "2_2") (pintype "passive"))
      (node (ref "U$1") (pin "80") (pinfunction "PTC7_80") (pintype "bidirectional"))
    )
    (net (code "115") (name "PTC10") (class "Default")
      (node (ref "JP4") (pin "2") (pinfunction "2_2") (pintype "passive"))
      (node (ref "U$1") (pin "52") (pinfunction "PTC10_52") (pintype "bidirectional"))
    )
    (net (code "116") (name "PTC11") (class "Default")
      (node (ref "JP3") (pin "2") (pinfunction "2_2") (pintype "passive"))
      (node (ref "U$1") (pin "51") (pinfunction "PTC11_51") (pintype "bidirectional"))
    )
    (net (code "117") (name "PTC12") (class "Default")
      (node (ref "JP2") (pin "2") (pinfunction "2_2") (pintype "passive"))
      (node (ref "U$1") (pin "50") (pinfunction "PTC12_50") (pintype "bidirectional"))
    )
    (net (code "118") (name "PTC13") (class "Default")
      (node (ref "JP1") (pin "2") (pinfunction "2_2") (pintype "passive"))
      (node (ref "U$1") (pin "49") (pinfunction "PTC13_49") (pintype "bidirectional"))
    )
    (net (code "119") (name "PTD5_{slash}_FTM2_CH3_{slash}_PWT_IN2") (class "Default")
      (node (ref "JP15") (pin "8") (pinfunction "8_8") (pintype "passive"))
      (node (ref "U$1") (pin "33") (pinfunction "PTD5_33") (pintype "bidirectional"))
    )
    (net (code "120") (name "PTD6_{slash}_FTM2_FLT2") (class "Default")
      (node (ref "JP15") (pin "7") (pinfunction "7_7") (pintype "passive"))
      (node (ref "U$1") (pin "32") (pinfunction "PTD6_32") (pintype "bidirectional"))
    )
    (net (code "121") (name "PTD7_{slash}_FTM2_FLT3") (class "Default")
      (node (ref "JP15") (pin "6") (pinfunction "6_6") (pintype "passive"))
      (node (ref "U$1") (pin "31") (pinfunction "PTD7_31") (pintype "bidirectional"))
    )
    (net (code "122") (name "PTD10_{slash}_FTM2_CH0") (class "Default")
      (node (ref "JP15") (pin "9") (pinfunction "9_9") (pintype "passive"))
      (node (ref "U$1") (pin "36") (pinfunction "PTD10_36") (pintype "bidirectional"))
    )
    (net (code "123") (name "PTE6_{slash}_ADC1_SE11") (class "Default")
      (node (ref "JP14") (pin "5") (pinfunction "5_5") (pintype "passive"))
      (node (ref "U$1") (pin "84") (pinfunction "PTE6_84") (pintype "bidirectional"))
    )
    (net (code "124") (name "PTE13_{slash}_FTM2_FLT0") (class "Default")
      (node (ref "JP15") (pin "2") (pinfunction "2_2") (pintype "passive"))
      (node (ref "U$1") (pin "7") (pinfunction "PTE13_7") (pintype "bidirectional"))
    )
    (net (code "125") (name "PWT_IN1_{slash}_FXIO_D5") (class "Default")
      (node (ref "J22") (pin "6") (pinfunction "6_6") (pintype "passive"))
      (node (ref "JP10") (pin "6") (pinfunction "6_6") (pintype "passive"))
      (node (ref "U$1") (pin "5") (pinfunction "PTE11_5") (pintype "bidirectional"))
    )
    (net (code "126") (name "RTC_CLK_OUT_{slash}_FTM2_CH4") (class "Default")
      (node (ref "JP15") (pin "5") (pinfunction "5_5") (pintype "passive"))
      (node (ref "U$1") (pin "25") (pinfunction "PTD13_25") (pintype "bidirectional"))
    )
    (net (code "127") (name "SPI0_MISO") (class "Default")
      (node (ref "J5") (pin "4") (pinfunction "4_4") (pintype "passive"))
      (node (ref "Q5") (pin "3") (pinfunction "D_3") (pintype "passive"))
      (node (ref "R34") (pin "1") (pinfunction "1_1") (pintype "passive"))
      (node (ref "U$1") (pin "93") (pinfunction "PTE1_93") (pintype "bidirectional"))
    )
    (net (code "128") (name "SPI0_MOSI") (class "Default")
      (node (ref "J5") (pin "5") (pinfunction "5_5") (pintype "passive"))
      (node (ref "Q6") (pin "3") (pinfunction "D_3") (pintype "passive"))
      (node (ref "R37") (pin "1") (pinfunction "1_1") (pintype "passive"))
      (node (ref "U$1") (pin "85") (pinfunction "PTE2_85") (pintype "bidirectional"))
    )
    (net (code "129") (name "SPI0_PCS0") (class "Default")
      (node (ref "Q7") (pin "3") (pinfunction "D_3") (pintype "passive"))
      (node (ref "R38") (pin "1") (pinfunction "1_1") (pintype "passive"))
      (node (ref "U$1") (pin "54") (pinfunction "PTB0_54") (pintype "bidirectional"))
    )
    (net (code "130") (name "SPI0_PCS3") (class "Default")
      (node (ref "J5") (pin "6") (pinfunction "6_6") (pintype "passive"))
      (node (ref "U$1") (pin "83") (pinfunction "PTA15_83") (pintype "bidirectional"))
    )
    (net (code "131") (name "SPI0_SCK") (class "Default")
      (node (ref "J5") (pin "3") (pinfunction "3_3") (pintype "passive"))
      (node (ref "Q4") (pin "3") (pinfunction "D_3") (pintype "passive"))
      (node (ref "R33") (pin "1") (pinfunction "1_1") (pintype "passive"))
      (node (ref "U$1") (pin "94") (pinfunction "PTE0_94") (pintype "bidirectional"))
    )
    (net (code "132") (name "UART0_RX") (class "Default")
      (node (ref "J7") (pin "4") (pinfunction "4_4") (pintype "passive"))
      (node (ref "U$1") (pin "73") (pinfunction "PTA2_73") (pintype "bidirectional"))
    )
    (net (code "133") (name "UART0_TX") (class "Default")
      (node (ref "J7") (pin "3") (pinfunction "3_3") (pintype "passive"))
      (node (ref "U$1") (pin "72") (pinfunction "PTA3_72") (pintype "bidirectional"))
    )
    (net (code "134") (name "UART1_CTS") (class "Default")
      (node (ref "U$1") (pin "58") (pinfunction "PTA6_58") (pintype "bidirectional"))
      (node (ref "U2") (pin "3") (pinfunction "RTS_3") (pintype "bidirectional"))
    )
    (net (code "135") (name "UART1_RTS") (class "Default")
      (node (ref "U$1") (pin "57") (pinfunction "PTA7_57") (pintype "bidirectional"))
      (node (ref "U2") (pin "11") (pinfunction "CTS_11") (pintype "bidirectional"))
    )
    (net (code "136") (name "UART1_RX") (class "Default")
      (node (ref "U$1") (pin "56") (pinfunction "PTC8_56") (pintype "bidirectional"))
      (node (ref "U2") (pin "1") (pinfunction "TXD_1") (pintype "output"))
    )
    (net (code "137") (name "UART1_TX") (class "Default")
      (node (ref "U$1") (pin "55") (pinfunction "PTC9_55") (pintype "bidirectional"))
      (node (ref "U2") (pin "5") (pinfunction "RXD_5") (pintype "input"))
    )
    (net (code "138") (name "UART2_CTS") (class "Default")
      (node (ref "J8") (pin "5") (pinfunction "5_5") (pintype "passive"))
      (node (ref "U$1") (pin "35") (pinfunction "PTD11_35") (pintype "bidirectional"))
    )
    (net (code "139") (name "UART2_RTS") (class "Default")
      (node (ref "J8") (pin "6") (pinfunction "6_6") (pintype "passive"))
      (node (ref "U$1") (pin "34") (pinfunction "PTD12_34") (pintype "bidirectional"))
    )
    (net (code "140") (name "UART2_RX") (class "Default")
      (node (ref "J8") (pin "4") (pinfunction "4_4") (pintype "passive"))
      (node (ref "U$1") (pin "20") (pinfunction "PTD17_20") (pintype "bidirectional"))
    )
    (net (code "141") (name "UART2_TX") (class "Default")
      (node (ref "J8") (pin "3") (pinfunction "3_3") (pintype "passive"))
      (node (ref "U$1") (pin "19") (pinfunction "PTE12_19") (pintype "bidirectional"))
    )
    (net (code "142") (name "VBUS") (class "Default")
      (node (ref "CN1") (pin "1") (pinfunction "VBUS_1") (pintype "power_in"))
      (node (ref "FB1") (pin "1") (pinfunction "P$1_1") (pintype "passive"))
    )
    (net (code "143") (name "unconnected-(CN1-ID-Pad4)") (class "Default")
      (node (ref "CN1") (pin "4") (pinfunction "ID_4") (pintype "bidirectional"))
    )
    (net (code "144") (name "unconnected-(J19-Pad2)") (class "Default")
      (node (ref "J19") (pin "2") (pinfunction "2_2") (pintype "passive"))
    )
    (net (code "145") (name "unconnected-(U2-DTR-Pad2)") (class "Default")
      (node (ref "U2") (pin "2") (pinfunction "DTR_2") (pintype "bidirectional"))
    )
    (net (code "146") (name "unconnected-(U3-AUX_CL-Pad7)") (class "Default")
      (node (ref "U3") (pin "7") (pinfunction "AUX_CL_7") (pintype "input"))
    )
    (net (code "147") (name "unconnected-(U3-AUX_DA-Pad21)") (class "Default")
      (node (ref "U3") (pin "21") (pinfunction "AUX_DA_21") (pintype "input"))
    )
    (net (code "148") (name "unconnected-(U3-RESV_19-Pad19)") (class "Default")
      (node (ref "U3") (pin "19") (pinfunction "RESV_19_19") (pintype "passive"))
    )
    (net (code "149") (name "unconnected-(VR1-NC-Pad4)") (class "Default")
      (node (ref "VR1") (pin "4") (pinfunction "NC_4") (pintype "no_connect"))
    )
    (net (code "150") (name "unconnected-(VR2-NC-Pad4)") (class "Default")
      (node (ref "VR2") (pin "4") (pinfunction "NC_4") (pintype "no_connect"))
    )
  )
)
